# homeboard10.net
KiCad netlist of a schematic drawn in EAGLE
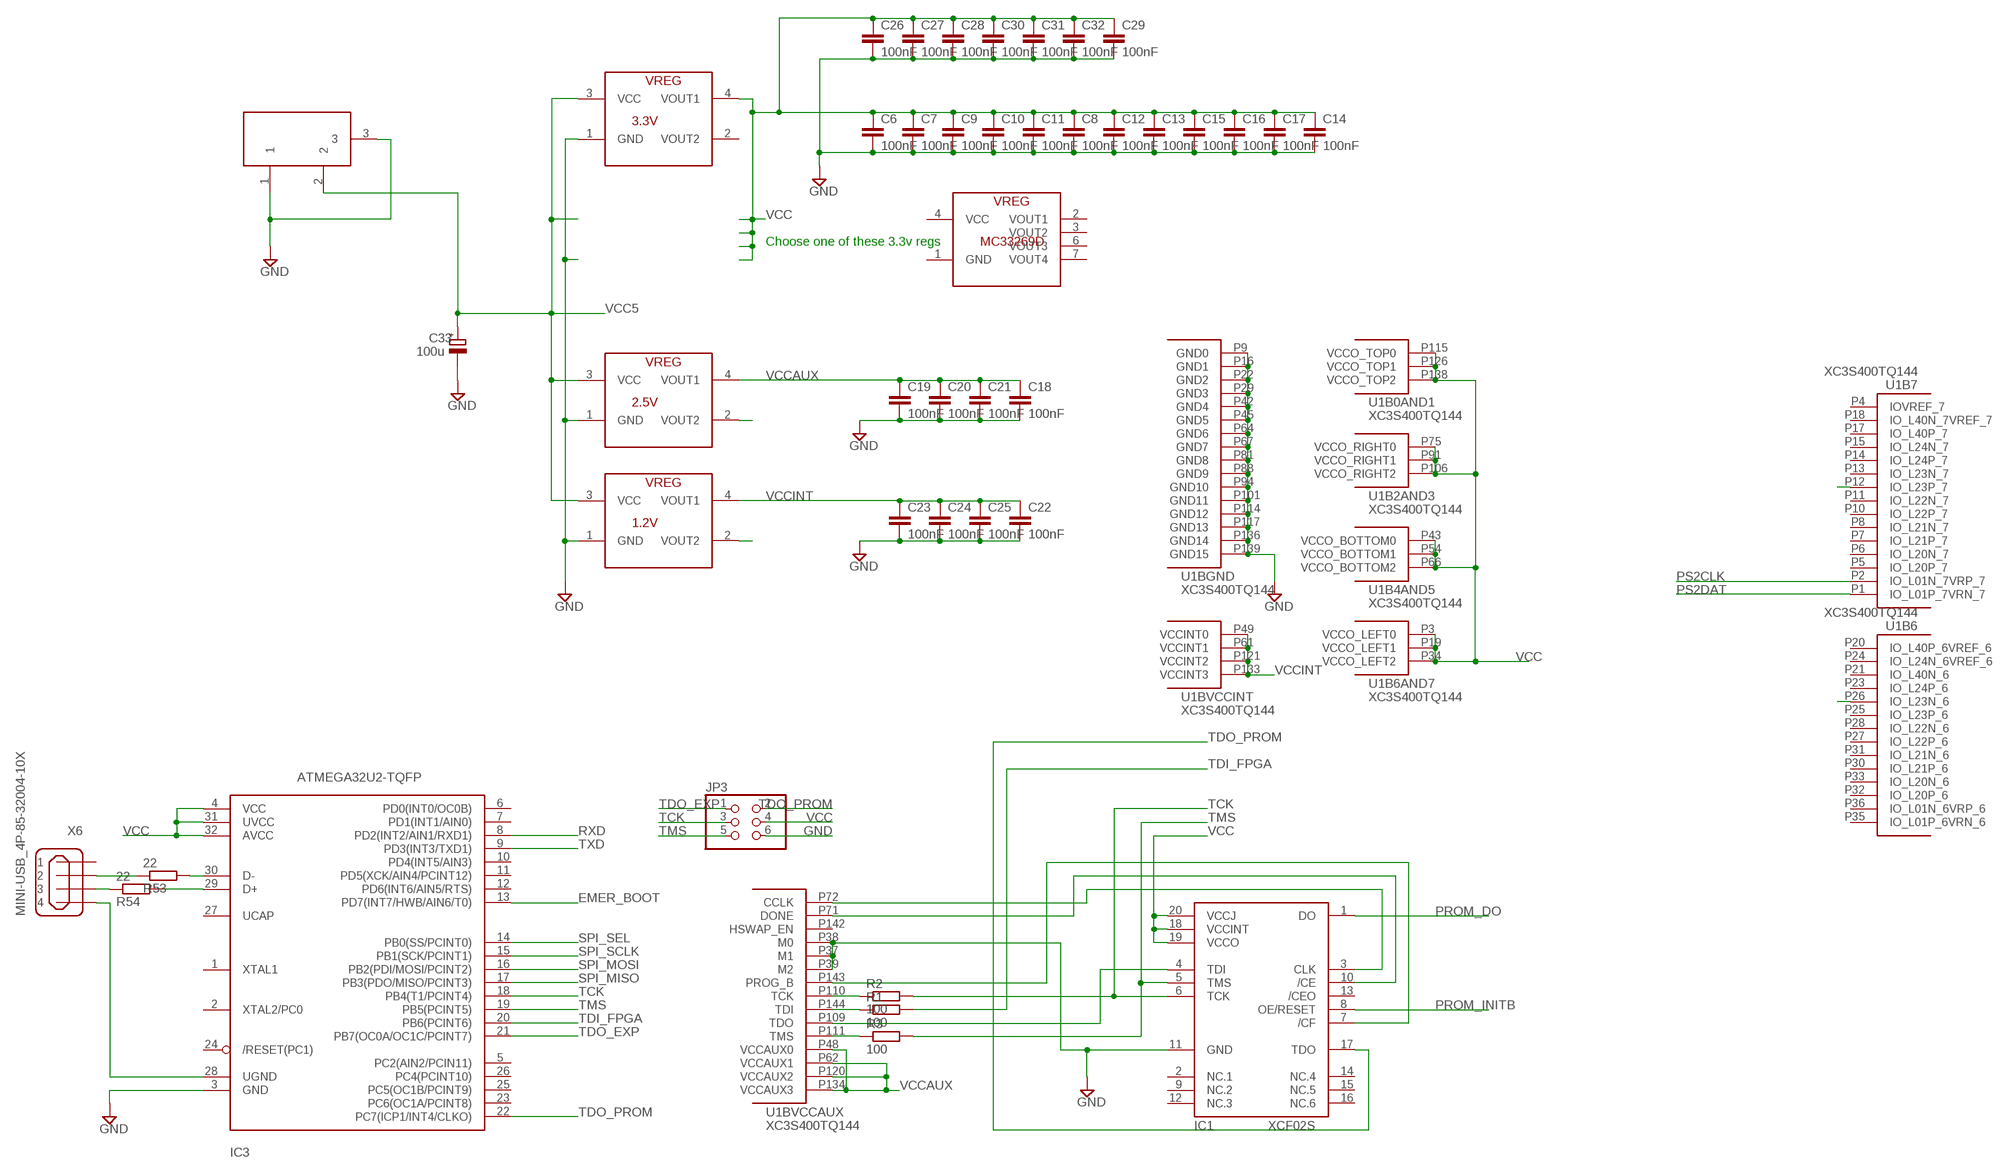
[diagram p0: schematic, sheet 1, part 1 of 3]
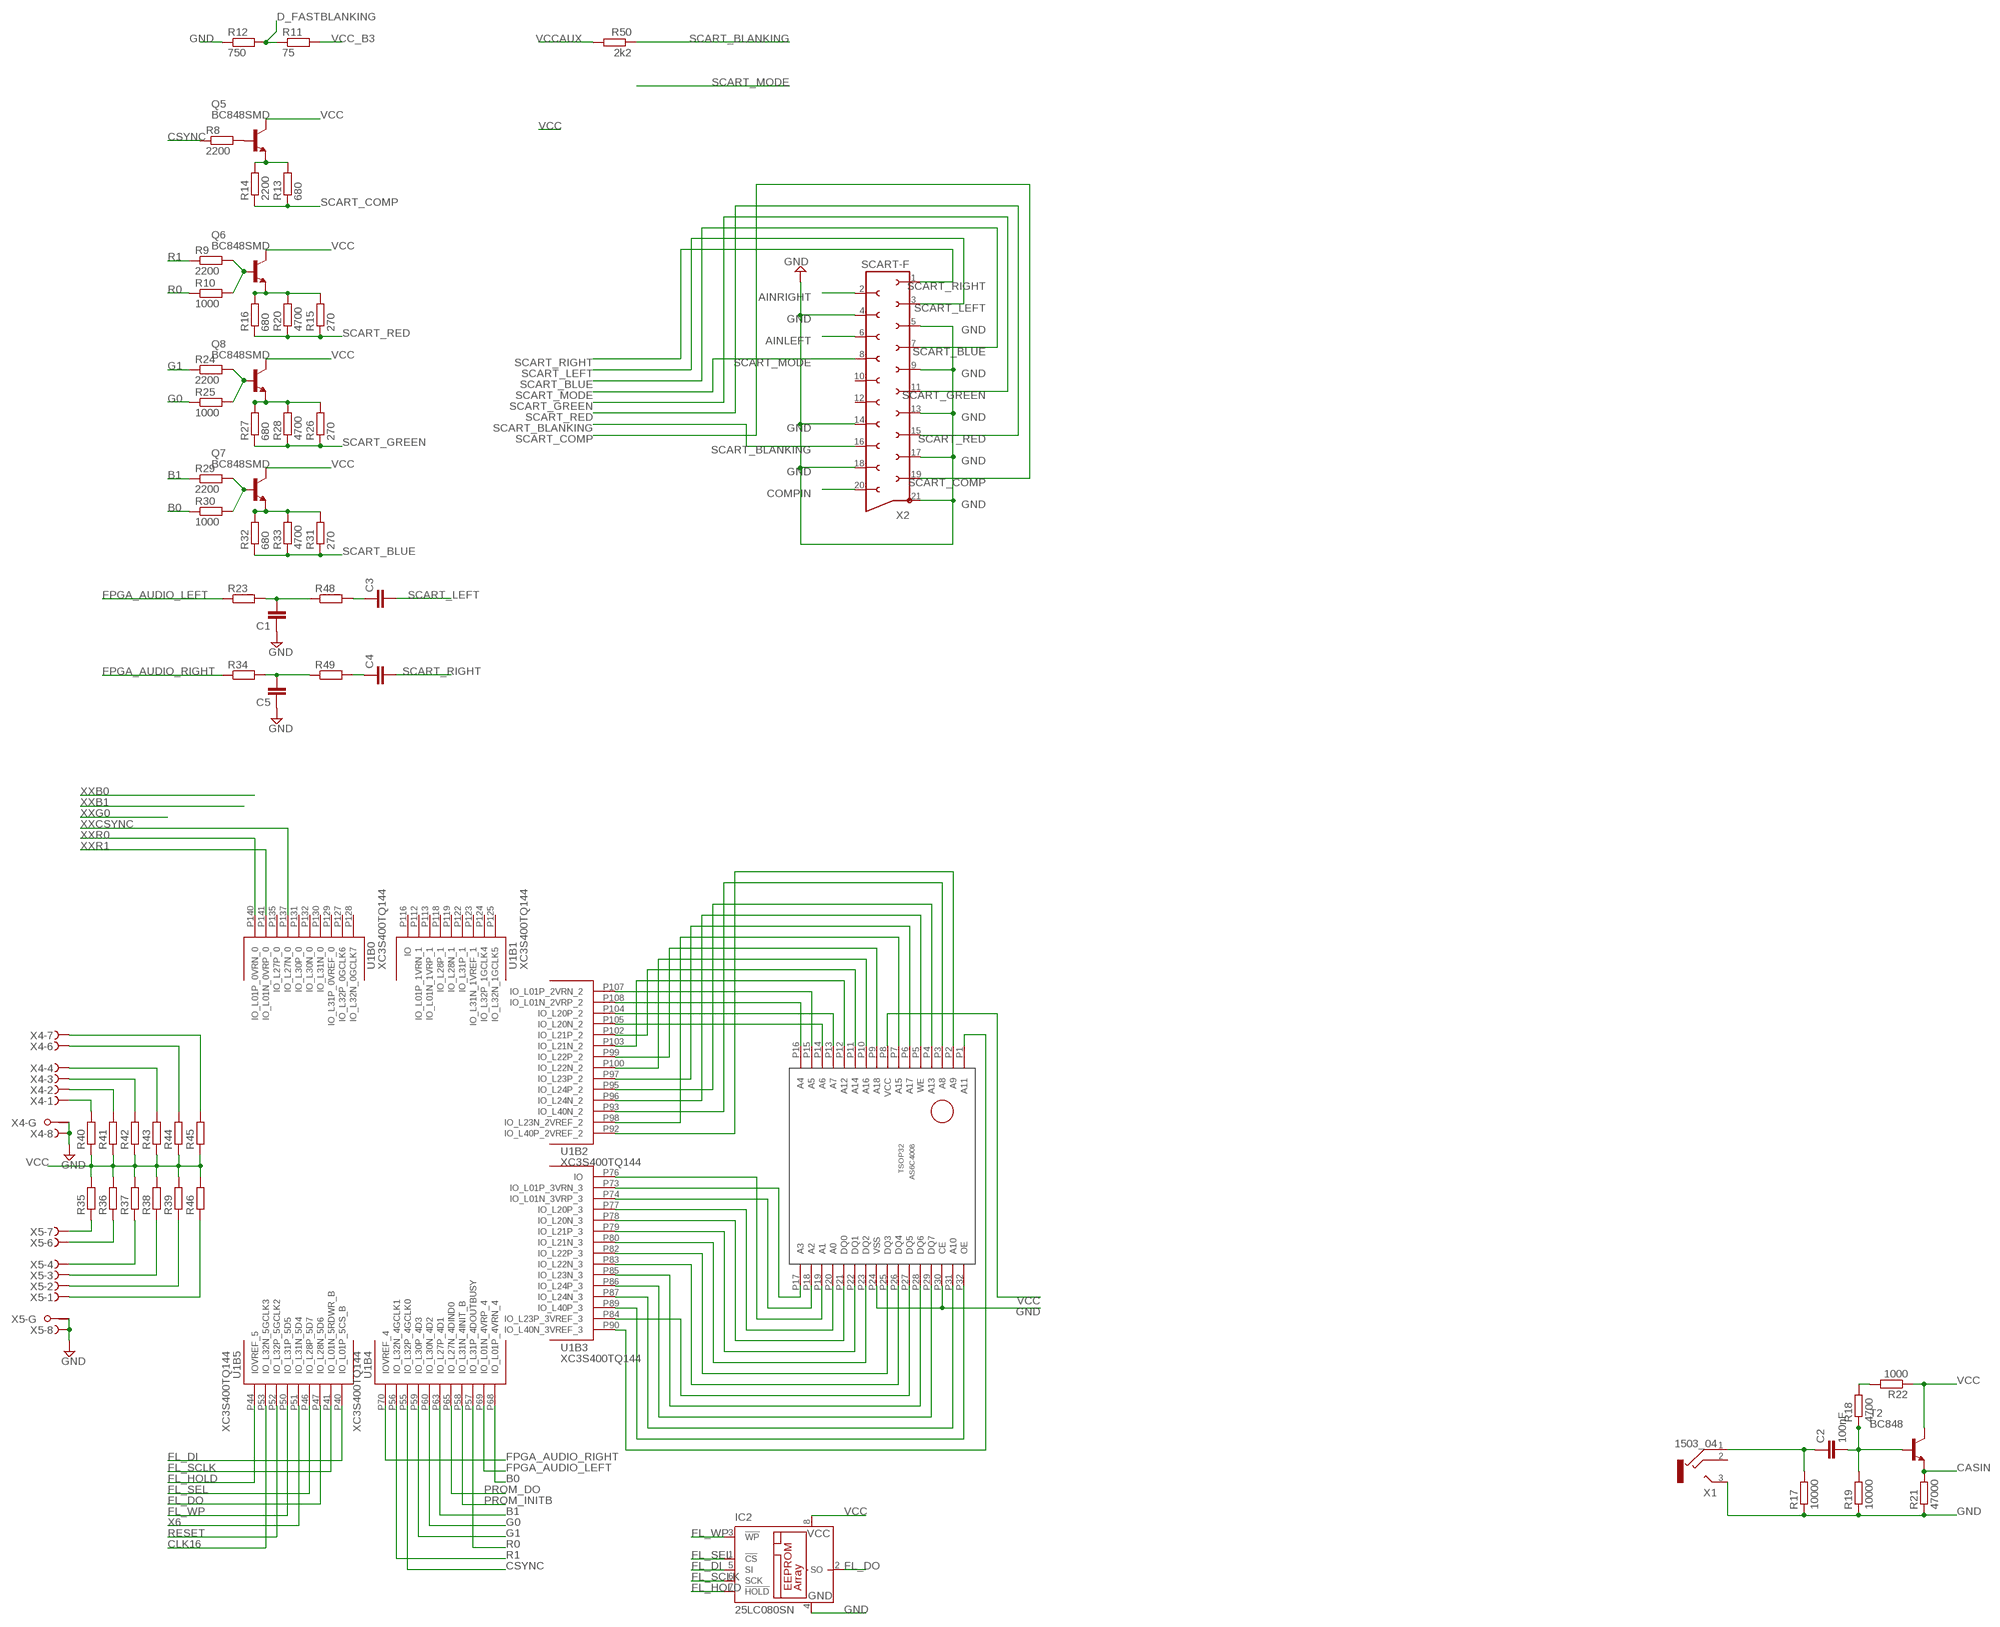
[diagram p1: schematic, sheet 1, part 2 of 3]
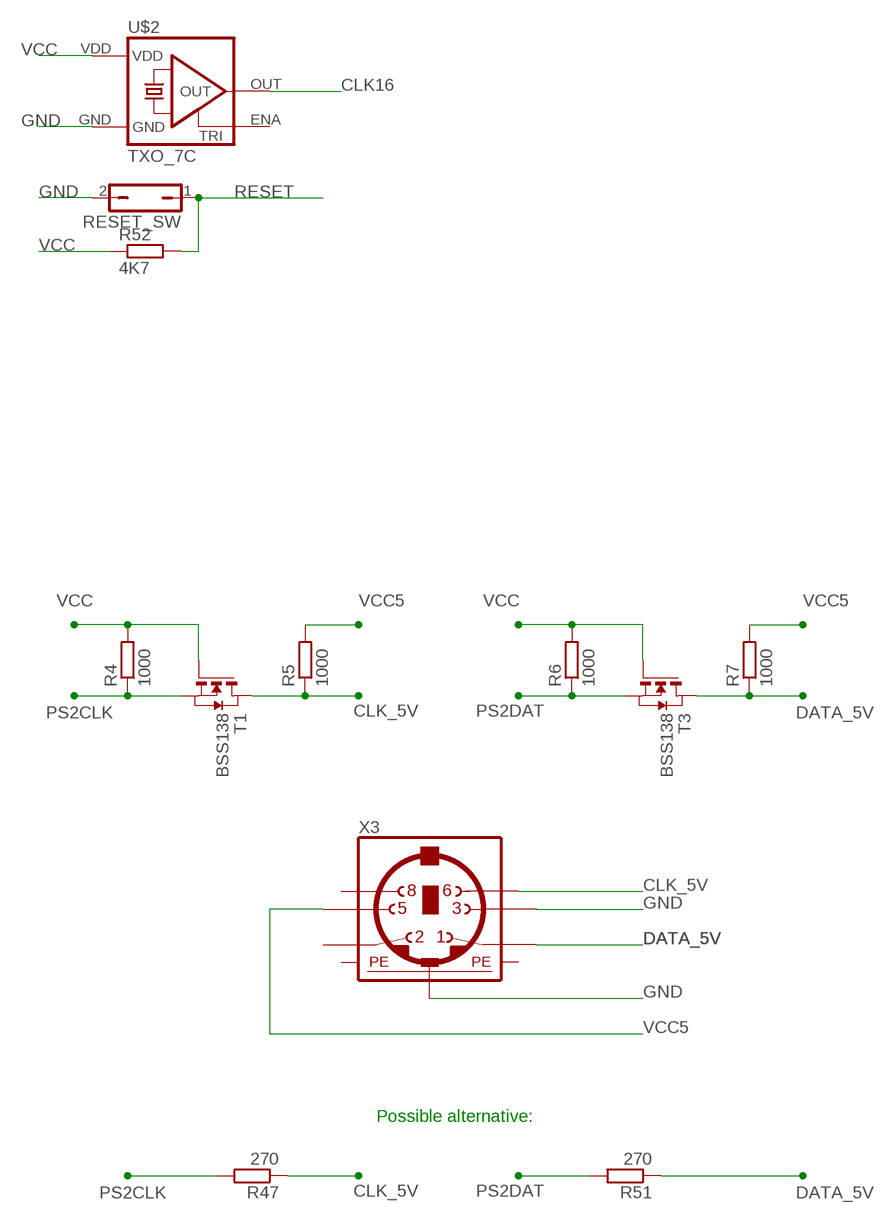
[diagram p2: schematic, sheet 1, part 3 of 3]

(export (version "E")
  (design (tool "Eeschema 10.0.6"))
  (components
    (comp (ref "C1")
      (value "C-EUC0603")
      (footprint "eagle-import:C0603")
      (libsource (lib "eagle-import") (part "resistor_C-EUC0603"))
    )
    (comp (ref "C2")
      (value "100nF")
      (footprint "eagle-import:C0603")
      (libsource (lib "eagle-import") (part "resistor_C-EUC0603"))
    )
    (comp (ref "C3")
      (value "C-EUC0603")
      (footprint "eagle-import:C0603")
      (libsource (lib "eagle-import") (part "resistor_C-EUC0603"))
    )
    (comp (ref "C4")
      (value "C-EUC0603")
      (footprint "eagle-import:C0603")
      (libsource (lib "eagle-import") (part "resistor_C-EUC0603"))
    )
    (comp (ref "C5")
      (value "C-EUC0603")
      (footprint "eagle-import:C0603")
      (libsource (lib "eagle-import") (part "resistor_C-EUC0603"))
    )
    (comp (ref "C6")
      (value "100nF")
      (footprint "eagle-import:C0603")
      (libsource (lib "eagle-import") (part "C-EUC0603"))
    )
    (comp (ref "C7")
      (value "100nF")
      (footprint "eagle-import:C0603")
      (libsource (lib "eagle-import") (part "C-EUC0603"))
    )
    (comp (ref "C8")
      (value "100nF")
      (footprint "eagle-import:C0603")
      (libsource (lib "eagle-import") (part "C-EUC0603"))
    )
    (comp (ref "C9")
      (value "100nF")
      (footprint "eagle-import:C0603")
      (libsource (lib "eagle-import") (part "C-EUC0603"))
    )
    (comp (ref "C10")
      (value "100nF")
      (footprint "eagle-import:C0603")
      (libsource (lib "eagle-import") (part "C-EUC0603"))
    )
    (comp (ref "C11")
      (value "100nF")
      (footprint "eagle-import:C0603")
      (libsource (lib "eagle-import") (part "C-EUC0603"))
    )
    (comp (ref "C12")
      (value "100nF")
      (footprint "eagle-import:C0603")
      (libsource (lib "eagle-import") (part "C-EUC0603"))
    )
    (comp (ref "C13")
      (value "100nF")
      (footprint "eagle-import:C0603")
      (libsource (lib "eagle-import") (part "C-EUC0603"))
    )
    (comp (ref "C14")
      (value "100nF")
      (footprint "eagle-import:C0603")
      (libsource (lib "eagle-import") (part "C-EUC0603"))
    )
    (comp (ref "C15")
      (value "100nF")
      (footprint "eagle-import:C0603")
      (libsource (lib "eagle-import") (part "C-EUC0603"))
    )
    (comp (ref "C16")
      (value "100nF")
      (footprint "eagle-import:C0603")
      (libsource (lib "eagle-import") (part "C-EUC0603"))
    )
    (comp (ref "C17")
      (value "100nF")
      (footprint "eagle-import:C0603")
      (libsource (lib "eagle-import") (part "C-EUC0603"))
    )
    (comp (ref "C18")
      (value "100nF")
      (footprint "eagle-import:C0603")
      (libsource (lib "eagle-import") (part "C-EUC0603"))
    )
    (comp (ref "C19")
      (value "100nF")
      (footprint "eagle-import:C0603")
      (libsource (lib "eagle-import") (part "C-EUC0603"))
    )
    (comp (ref "C20")
      (value "100nF")
      (footprint "eagle-import:C0603")
      (libsource (lib "eagle-import") (part "C-EUC0603"))
    )
    (comp (ref "C21")
      (value "100nF")
      (footprint "eagle-import:C0603")
      (libsource (lib "eagle-import") (part "C-EUC0603"))
    )
    (comp (ref "C22")
      (value "100nF")
      (footprint "eagle-import:C0603")
      (libsource (lib "eagle-import") (part "C-EUC0603"))
    )
    (comp (ref "C23")
      (value "100nF")
      (footprint "eagle-import:C0603")
      (libsource (lib "eagle-import") (part "C-EUC0603"))
    )
    (comp (ref "C24")
      (value "100nF")
      (footprint "eagle-import:C0603")
      (libsource (lib "eagle-import") (part "C-EUC0603"))
    )
    (comp (ref "C25")
      (value "100nF")
      (footprint "eagle-import:C0603")
      (libsource (lib "eagle-import") (part "C-EUC0603"))
    )
    (comp (ref "C26")
      (value "100nF")
      (footprint "eagle-import:C0603")
      (libsource (lib "eagle-import") (part "C-EUC0603"))
    )
    (comp (ref "C27")
      (value "100nF")
      (footprint "eagle-import:C0603")
      (libsource (lib "eagle-import") (part "C-EUC0603"))
    )
    (comp (ref "C28")
      (value "100nF")
      (footprint "eagle-import:C0603")
      (libsource (lib "eagle-import") (part "C-EUC0603"))
    )
    (comp (ref "C29")
      (value "100nF")
      (footprint "eagle-import:C0603")
      (libsource (lib "eagle-import") (part "C-EUC0603"))
    )
    (comp (ref "C30")
      (value "100nF")
      (footprint "eagle-import:C0603")
      (libsource (lib "eagle-import") (part "C-EUC0603"))
    )
    (comp (ref "C31")
      (value "100nF")
      (footprint "eagle-import:C0603")
      (libsource (lib "eagle-import") (part "C-EUC0603"))
    )
    (comp (ref "C32")
      (value "100nF")
      (footprint "eagle-import:C0603")
      (libsource (lib "eagle-import") (part "C-EUC0603"))
    )
    (comp (ref "C33")
      (value "100u")
      (footprint "eagle-import:PANASONIC_D")
      (libsource (lib "eagle-import") (part "CPOL-EUD"))
    )
    (comp (ref "IC1")
      (value "XCF02S")
      (footprint "eagle-import:VO20")
      (libsource (lib "eagle-import") (part "XCF02S"))
    )
    (comp (ref "IC2")
      (value "25LC080SN")
      (footprint "eagle-import:SO-08")
      (fields (field (name "MF") "MICROCHIP") (field (name "MPN") "25LC080/SN"))
      (libsource (lib "eagle-import") (part "25SNLC080"))
    )
    (comp (ref "IC3")
      (value "ATMEGA32U2-TQFP")
      (footprint "eagle-import:TQFP32-08")
      (libsource (lib "eagle-import") (part "ATMEGA32U2-TQFP"))
    )
    (comp (ref "JP3")
      (value "PINHD-2X3")
      (footprint "eagle-import:2X03")
      (libsource (lib "eagle-import") (part "PINHD-2X3"))
    )
    (comp (ref "Q5")
      (value "BC848SMD")
      (footprint "eagle-import:SOT23")
      (libsource (lib "eagle-import") (part "BC848SMD"))
    )
    (comp (ref "Q6")
      (value "BC848SMD")
      (footprint "eagle-import:SOT23")
      (libsource (lib "eagle-import") (part "BC848SMD"))
    )
    (comp (ref "Q7")
      (value "BC848SMD")
      (footprint "eagle-import:SOT23")
      (libsource (lib "eagle-import") (part "BC848SMD"))
    )
    (comp (ref "Q8")
      (value "BC848SMD")
      (footprint "eagle-import:SOT23")
      (libsource (lib "eagle-import") (part "BC848SMD"))
    )
    (comp (ref "R1")
      (value "100")
      (footprint "eagle-import:R0805")
      (libsource (lib "eagle-import") (part "R-EU_R0805"))
    )
    (comp (ref "R2")
      (value "100")
      (footprint "eagle-import:R0805")
      (libsource (lib "eagle-import") (part "R-EU_R0805"))
    )
    (comp (ref "R3")
      (value "100")
      (footprint "eagle-import:R0805")
      (libsource (lib "eagle-import") (part "R-EU_R0805"))
    )
    (comp (ref "R4")
      (value "1000")
      (footprint "eagle-import:R0805")
      (libsource (lib "eagle-import") (part "R-EU_R0805"))
    )
    (comp (ref "R5")
      (value "1000")
      (footprint "eagle-import:R0805")
      (libsource (lib "eagle-import") (part "R-EU_R0805"))
    )
    (comp (ref "R6")
      (value "1000")
      (footprint "eagle-import:R0805")
      (libsource (lib "eagle-import") (part "R-EU_R0805"))
    )
    (comp (ref "R7")
      (value "1000")
      (footprint "eagle-import:R0805")
      (libsource (lib "eagle-import") (part "R-EU_R0805"))
    )
    (comp (ref "R8")
      (value "2200")
      (footprint "eagle-import:R0805")
      (libsource (lib "eagle-import") (part "R-EU_R0805"))
    )
    (comp (ref "R9")
      (value "2200")
      (footprint "eagle-import:R0805")
      (libsource (lib "eagle-import") (part "R-EU_R0805"))
    )
    (comp (ref "R10")
      (value "1000")
      (footprint "eagle-import:R0805")
      (libsource (lib "eagle-import") (part "R-EU_R0805"))
    )
    (comp (ref "R11")
      (value "75")
      (footprint "eagle-import:R0805")
      (libsource (lib "eagle-import") (part "R-EU_R0805"))
    )
    (comp (ref "R12")
      (value "750")
      (footprint "eagle-import:R0805")
      (libsource (lib "eagle-import") (part "R-EU_R0805"))
    )
    (comp (ref "R13")
      (value "680")
      (footprint "eagle-import:R0805")
      (libsource (lib "eagle-import") (part "R-EU_R0805"))
    )
    (comp (ref "R14")
      (value "2200")
      (footprint "eagle-import:R0805")
      (libsource (lib "eagle-import") (part "R-EU_R0805"))
    )
    (comp (ref "R15")
      (value "270")
      (footprint "eagle-import:R0805")
      (libsource (lib "eagle-import") (part "R-EU_R0805"))
    )
    (comp (ref "R16")
      (value "680")
      (footprint "eagle-import:R0805")
      (libsource (lib "eagle-import") (part "R-EU_R0805"))
    )
    (comp (ref "R17")
      (value "10000")
      (footprint "eagle-import:R0805")
      (libsource (lib "eagle-import") (part "R-EU_R0805"))
    )
    (comp (ref "R18")
      (value "4700")
      (footprint "eagle-import:R0805")
      (libsource (lib "eagle-import") (part "R-EU_R0805"))
    )
    (comp (ref "R19")
      (value "10000")
      (footprint "eagle-import:R0805")
      (libsource (lib "eagle-import") (part "R-EU_R0805"))
    )
    (comp (ref "R20")
      (value "4700")
      (footprint "eagle-import:R0805")
      (libsource (lib "eagle-import") (part "R-EU_R0805"))
    )
    (comp (ref "R21")
      (value "47000")
      (footprint "eagle-import:R0805")
      (libsource (lib "eagle-import") (part "R-EU_R0805"))
    )
    (comp (ref "R22")
      (value "1000")
      (footprint "eagle-import:R0805")
      (libsource (lib "eagle-import") (part "R-EU_R0805"))
    )
    (comp (ref "R23")
      (value "R-EU_M0805")
      (footprint "eagle-import:M0805")
      (libsource (lib "eagle-import") (part "resistor_R-EU_M0805"))
    )
    (comp (ref "R24")
      (value "2200")
      (footprint "eagle-import:R0805")
      (libsource (lib "eagle-import") (part "R-EU_R0805"))
    )
    (comp (ref "R25")
      (value "1000")
      (footprint "eagle-import:R0805")
      (libsource (lib "eagle-import") (part "R-EU_R0805"))
    )
    (comp (ref "R26")
      (value "270")
      (footprint "eagle-import:R0805")
      (libsource (lib "eagle-import") (part "R-EU_R0805"))
    )
    (comp (ref "R27")
      (value "680")
      (footprint "eagle-import:R0805")
      (libsource (lib "eagle-import") (part "R-EU_R0805"))
    )
    (comp (ref "R28")
      (value "4700")
      (footprint "eagle-import:R0805")
      (libsource (lib "eagle-import") (part "R-EU_R0805"))
    )
    (comp (ref "R29")
      (value "2200")
      (footprint "eagle-import:R0805")
      (libsource (lib "eagle-import") (part "R-EU_R0805"))
    )
    (comp (ref "R30")
      (value "1000")
      (footprint "eagle-import:R0805")
      (libsource (lib "eagle-import") (part "R-EU_R0805"))
    )
    (comp (ref "R31")
      (value "270")
      (footprint "eagle-import:R0805")
      (libsource (lib "eagle-import") (part "R-EU_R0805"))
    )
    (comp (ref "R32")
      (value "680")
      (footprint "eagle-import:R0805")
      (libsource (lib "eagle-import") (part "R-EU_R0805"))
    )
    (comp (ref "R33")
      (value "4700")
      (footprint "eagle-import:R0805")
      (libsource (lib "eagle-import") (part "R-EU_R0805"))
    )
    (comp (ref "R34")
      (value "R-EU_M0805")
      (footprint "eagle-import:M0805")
      (libsource (lib "eagle-import") (part "resistor_R-EU_M0805"))
    )
    (comp (ref "R35")
      (value "R-EU_M0805")
      (footprint "eagle-import:M0805")
      (libsource (lib "eagle-import") (part "resistor_R-EU_M0805"))
    )
    (comp (ref "R36")
      (value "R-EU_M0805")
      (footprint "eagle-import:M0805")
      (libsource (lib "eagle-import") (part "resistor_R-EU_M0805"))
    )
    (comp (ref "R37")
      (value "R-EU_M0805")
      (footprint "eagle-import:M0805")
      (libsource (lib "eagle-import") (part "resistor_R-EU_M0805"))
    )
    (comp (ref "R38")
      (value "R-EU_M0805")
      (footprint "eagle-import:M0805")
      (libsource (lib "eagle-import") (part "resistor_R-EU_M0805"))
    )
    (comp (ref "R39")
      (value "R-EU_M0805")
      (footprint "eagle-import:M0805")
      (libsource (lib "eagle-import") (part "resistor_R-EU_M0805"))
    )
    (comp (ref "R40")
      (value "R-EU_M0805")
      (footprint "eagle-import:M0805")
      (libsource (lib "eagle-import") (part "resistor_R-EU_M0805"))
    )
    (comp (ref "R41")
      (value "R-EU_M0805")
      (footprint "eagle-import:M0805")
      (libsource (lib "eagle-import") (part "resistor_R-EU_M0805"))
    )
    (comp (ref "R42")
      (value "R-EU_M0805")
      (footprint "eagle-import:M0805")
      (libsource (lib "eagle-import") (part "resistor_R-EU_M0805"))
    )
    (comp (ref "R43")
      (value "R-EU_M0805")
      (footprint "eagle-import:M0805")
      (libsource (lib "eagle-import") (part "resistor_R-EU_M0805"))
    )
    (comp (ref "R44")
      (value "R-EU_M0805")
      (footprint "eagle-import:M0805")
      (libsource (lib "eagle-import") (part "resistor_R-EU_M0805"))
    )
    (comp (ref "R45")
      (value "R-EU_M0805")
      (footprint "eagle-import:M0805")
      (libsource (lib "eagle-import") (part "resistor_R-EU_M0805"))
    )
    (comp (ref "R46")
      (value "R-EU_M0805")
      (footprint "eagle-import:M0805")
      (libsource (lib "eagle-import") (part "resistor_R-EU_M0805"))
    )
    (comp (ref "R47")
      (value "270")
      (footprint "eagle-import:R0805")
      (libsource (lib "eagle-import") (part "R-EU_R0805"))
    )
    (comp (ref "R48")
      (value "R-EU_M0805")
      (footprint "eagle-import:M0805")
      (libsource (lib "eagle-import") (part "resistor_R-EU_M0805"))
    )
    (comp (ref "R49")
      (value "R-EU_M0805")
      (footprint "eagle-import:M0805")
      (libsource (lib "eagle-import") (part "resistor_R-EU_M0805"))
    )
    (comp (ref "R50")
      (value "2k2")
      (footprint "eagle-import:M0805")
      (libsource (lib "eagle-import") (part "resistor_R-EU_M0805"))
    )
    (comp (ref "R51")
      (value "270")
      (footprint "eagle-import:R0805")
      (libsource (lib "eagle-import") (part "R-EU_R0805"))
    )
    (comp (ref "R52")
      (value "4K7")
      (footprint "eagle-import:M0805")
      (libsource (lib "eagle-import") (part "resistor_R-EU_M0805"))
    )
    (comp (ref "R53")
      (value "22")
      (footprint "eagle-import:R0805")
      (libsource (lib "eagle-import") (part "R-EU_R0805"))
    )
    (comp (ref "R54")
      (value "22")
      (footprint "eagle-import:R0805")
      (libsource (lib "eagle-import") (part "R-EU_R0805"))
    )
    (comp (ref "REG1.2")
      (value "1.2V")
      (footprint "eagle-import:SOT223")
      (libsource (lib "eagle-import") (part "NX1117"))
    )
    (comp (ref "REG2.5")
      (value "2.5V")
      (footprint "eagle-import:SOT223")
      (libsource (lib "eagle-import") (part "NX1117"))
    )
    (comp (ref "RESET_SW")
      (value "JP1Q")
      (footprint "eagle-import:JP1")
      (libsource (lib "eagle-import") (part "JP1Q"))
    )
    (comp (ref "T1")
      (value "BSS138")
      (footprint "eagle-import:SOT-23")
      (libsource (lib "eagle-import") (part "NMOSSOT23"))
    )
    (comp (ref "T2")
      (value "BC848")
      (footprint "eagle-import:SOT23")
      (libsource (lib "eagle-import") (part "BC848"))
    )
    (comp (ref "T3")
      (value "BSS138")
      (footprint "eagle-import:SOT-23")
      (libsource (lib "eagle-import") (part "NMOSSOT23"))
    )
    (comp (ref "U$1")
      (value "AS6C4008")
      (footprint "eagle-import:TSOP32")
      (libsource (lib "eagle-import") (part "AS6C4008"))
    )
    (comp (ref "U$2")
      (value "TXO_7C")
      (footprint "eagle-import:OSC_7C")
      (libsource (lib "eagle-import") (part "TXO_7C"))
    )
    (comp (ref "U$4")
      (value "3.3V")
      (footprint "eagle-import:SOT223")
      (libsource (lib "eagle-import") (part "NX1117"))
    )
    (comp (ref "U$5")
      (value "MC33269D")
      (footprint "eagle-import:SO8")
      (libsource (lib "eagle-import") (part "MC33269D"))
    )
    (comp (ref "U1")
      (value "XC3S400TQ144")
      (footprint "eagle-import:TQ144")
      (libsource (lib "eagle-import") (part "XC3S400TQ144"))
    )
    (comp (ref "X1")
      (value "1503_04")
      (footprint "eagle-import:1503_04")
      (libsource (lib "eagle-import") (part "1503_04"))
    )
    (comp (ref "X2")
      (value "SCART-F")
      (footprint "eagle-import:SCART-F")
      (libsource (lib "eagle-import") (part "SCART-F"))
    )
    (comp (ref "X3")
      (value "MINI_DIN_6")
      (footprint "eagle-import:M_DIN6")
      (libsource (lib "eagle-import") (part "MINI_DIN_6"))
    )
    (comp (ref "X4")
      (value "F09HPS")
      (footprint "eagle-import:F09HP")
      (libsource (lib "eagle-import") (part "F09HPS"))
    )
    (comp (ref "X5")
      (value "F09HPS")
      (footprint "eagle-import:F09HP")
      (libsource (lib "eagle-import") (part "F09HPS"))
    )
    (comp (ref "X6")
      (value "MINI-USB_4P-85-32004-10X")
      (footprint "eagle-import:85-32004-10X")
      (libsource (lib "eagle-import") (part "MINI-USB_4P-85-32004-10X"))
    )
    (comp (ref "X8")
      (value "DC21MMX")
      (footprint "eagle-import:DC-21MM")
      (libsource (lib "eagle-import") (part "DC21MMX"))
    )
  )
  (nets
    (net (code "1") (name "/AINLEFT") (class "Default")
      (node (ref "X2") (pin "6") (pinfunction "6_6") (pintype "passive"))
    )
    (net (code "2") (name "/AINRIGHT") (class "Default")
      (node (ref "X2") (pin "2") (pinfunction "2_2") (pintype "passive"))
    )
    (net (code "3") (name "/B0") (class "Default")
      (node (ref "R30") (pin "1") (pinfunction "1_1") (pintype "passive"))
      (node (ref "U1") (pin "P68") (pinfunction "IO_L01P_4VRN_4_P68") (pintype "bidirectional"))
    )
    (net (code "4") (name "/B1") (class "Default")
      (node (ref "R29") (pin "1") (pinfunction "1_1") (pintype "passive"))
      (node (ref "U1") (pin "P63") (pinfunction "IO_L27P_4D1_P63") (pintype "bidirectional"))
    )
    (net (code "5") (name "/CASIN") (class "Default")
      (node (ref "R21") (pin "2") (pinfunction "2_2") (pintype "passive"))
      (node (ref "T2") (pin "2") (pinfunction "E_2") (pintype "passive"))
    )
    (net (code "6") (name "/CLK16") (class "Default")
      (node (ref "U$2") (pin "OUT") (pinfunction "OUT_OUT") (pintype "output"))
      (node (ref "U1") (pin "P53") (pinfunction "IO_L32N_5GCLK3_P53") (pintype "bidirectional"))
    )
    (net (code "7") (name "/CLK_5V") (class "Default")
      (node (ref "R47") (pin "1") (pinfunction "1_1") (pintype "passive"))
      (node (ref "R5") (pin "1") (pinfunction "1_1") (pintype "passive"))
      (node (ref "T1") (pin "1") (pinfunction "D_1") (pintype "passive"))
      (node (ref "X3") (pin "6") (pinfunction "6_6") (pintype "passive"))
    )
    (net (code "8") (name "/COMPIN") (class "Default")
      (node (ref "X2") (pin "20") (pinfunction "20_20") (pintype "passive"))
    )
    (net (code "9") (name "/CSYNC") (class "Default")
      (node (ref "R8") (pin "1") (pinfunction "1_1") (pintype "passive"))
      (node (ref "U1") (pin "P55") (pinfunction "IO_L32P_4GCLK0_P55") (pintype "bidirectional"))
    )
    (net (code "10") (name "/DATA_5V") (class "Default")
      (node (ref "R51") (pin "1") (pinfunction "1_1") (pintype "passive"))
      (node (ref "R7") (pin "1") (pinfunction "1_1") (pintype "passive"))
      (node (ref "T3") (pin "1") (pinfunction "D_1") (pintype "passive"))
      (node (ref "X3") (pin "1") (pinfunction "1_1") (pintype "passive"))
    )
    (net (code "11") (name "/D_FASTBLANKING") (class "Default")
      (node (ref "R11") (pin "1") (pinfunction "1_1") (pintype "passive"))
      (node (ref "R12") (pin "2") (pinfunction "2_2") (pintype "passive"))
    )
    (net (code "12") (name "/EMER_BOOT") (class "Default")
      (node (ref "IC3") (pin "13") (pinfunction "PD7(INT7/HWB/AIN6/T0)_13") (pintype "bidirectional"))
    )
    (net (code "13") (name "/FL_DI") (class "Default")
      (node (ref "IC2") (pin "5") (pinfunction "SI_5") (pintype "input"))
      (node (ref "U1") (pin "P40") (pinfunction "IO_L01P_5CS_B_P40") (pintype "bidirectional"))
    )
    (net (code "14") (name "/FL_DO") (class "Default")
      (node (ref "IC2") (pin "2") (pinfunction "SO_2") (pintype "bidirectional"))
      (node (ref "U1") (pin "P47") (pinfunction "IO_L28N_5D6_P47") (pintype "bidirectional"))
    )
    (net (code "15") (name "/FL_HOLD") (class "Default")
      (node (ref "IC2") (pin "7") (pinfunction "~{HOLD}_7") (pintype "input"))
      (node (ref "U1") (pin "P44") (pinfunction "IOVREF_5_P44") (pintype "bidirectional"))
    )
    (net (code "16") (name "/FL_SCLK") (class "Default")
      (node (ref "IC2") (pin "6") (pinfunction "SCK_6") (pintype "input"))
      (node (ref "U1") (pin "P41") (pinfunction "IO_L01N_5RDWR_B_P41") (pintype "bidirectional"))
    )
    (net (code "17") (name "/FL_SEL") (class "Default")
      (node (ref "IC2") (pin "1") (pinfunction "~{CS}_1") (pintype "input"))
      (node (ref "U1") (pin "P46") (pinfunction "IO_L28P_5D7_P46") (pintype "bidirectional"))
    )
    (net (code "18") (name "/FL_WP") (class "Default")
      (node (ref "IC2") (pin "3") (pinfunction "~{WP}_3") (pintype "input"))
      (node (ref "U1") (pin "P50") (pinfunction "IO_L31P_5D5_P50") (pintype "bidirectional"))
    )
    (net (code "19") (name "/FPGA_AUDIO_LEFT") (class "Default")
      (node (ref "R23") (pin "1") (pinfunction "1_1") (pintype "passive"))
      (node (ref "U1") (pin "P69") (pinfunction "IO_L01N_4VRP_4_P69") (pintype "bidirectional"))
    )
    (net (code "20") (name "/FPGA_AUDIO_RIGHT") (class "Default")
      (node (ref "R34") (pin "1") (pinfunction "1_1") (pintype "passive"))
      (node (ref "U1") (pin "P70") (pinfunction "IOVREF_4_P70") (pintype "bidirectional"))
    )
    (net (code "21") (name "/G0") (class "Default")
      (node (ref "R25") (pin "1") (pinfunction "1_1") (pintype "passive"))
      (node (ref "U1") (pin "P60") (pinfunction "IO_L30N_4D2_P60") (pintype "bidirectional"))
    )
    (net (code "22") (name "/G1") (class "Default")
      (node (ref "R24") (pin "1") (pinfunction "1_1") (pintype "passive"))
      (node (ref "U1") (pin "P59") (pinfunction "IO_L30P_4D3_P59") (pintype "bidirectional"))
    )
    (net (code "23") (name "/PE1") (class "Default")
      (node (ref "X3") (pin "SH1") (pinfunction "PE1_SH1") (pintype "power_in"))
    )
    (net (code "24") (name "/PE3") (class "Default")
      (node (ref "X3") (pin "SH3") (pinfunction "PE3_SH3") (pintype "power_in"))
    )
    (net (code "25") (name "/PROM_DO") (class "Default")
      (node (ref "IC1") (pin "1") (pinfunction "DO_1") (pintype "bidirectional"))
      (node (ref "U1") (pin "P65") (pinfunction "IO_L27N_4DIND0_P65") (pintype "bidirectional"))
    )
    (net (code "26") (name "/PROM_INITB") (class "Default")
      (node (ref "IC1") (pin "8") (pinfunction "OE/RESET_8") (pintype "bidirectional"))
      (node (ref "U1") (pin "P58") (pinfunction "IO_L31N_4INIT_B_P58") (pintype "bidirectional"))
    )
    (net (code "27") (name "/PS2CLK") (class "Default")
      (node (ref "R4") (pin "1") (pinfunction "1_1") (pintype "passive"))
      (node (ref "R47") (pin "2") (pinfunction "2_2") (pintype "passive"))
      (node (ref "T1") (pin "2") (pinfunction "S_2") (pintype "passive"))
      (node (ref "U1") (pin "P2") (pinfunction "IO_L01N_7VRP_7_P2") (pintype "bidirectional"))
    )
    (net (code "28") (name "/PS2DAT") (class "Default")
      (node (ref "R51") (pin "2") (pinfunction "2_2") (pintype "passive"))
      (node (ref "R6") (pin "1") (pinfunction "1_1") (pintype "passive"))
      (node (ref "T3") (pin "2") (pinfunction "S_2") (pintype "passive"))
      (node (ref "U1") (pin "P1") (pinfunction "IO_L01P_7VRN_7_P1") (pintype "bidirectional"))
    )
    (net (code "29") (name "/R0") (class "Default")
      (node (ref "R10") (pin "1") (pinfunction "1_1") (pintype "passive"))
      (node (ref "U1") (pin "P57") (pinfunction "IO_L31P_4DOUTBUSY_P57") (pintype "bidirectional"))
    )
    (net (code "30") (name "/R1") (class "Default")
      (node (ref "R9") (pin "1") (pinfunction "1_1") (pintype "passive"))
      (node (ref "U1") (pin "P56") (pinfunction "IO_L32N_4GCLK1_P56") (pintype "bidirectional"))
    )
    (net (code "31") (name "/RESET") (class "Default")
      (node (ref "R52") (pin "2") (pinfunction "2_2") (pintype "passive"))
      (node (ref "RESET_SW") (pin "1") (pinfunction "1_1") (pintype "passive"))
      (node (ref "U1") (pin "P52") (pinfunction "IO_L32P_5GCLK2_P52") (pintype "bidirectional"))
    )
    (net (code "32") (name "/RXD") (class "Default")
      (node (ref "IC3") (pin "8") (pinfunction "PD2(INT2/AIN1/RXD1)_8") (pintype "bidirectional"))
    )
    (net (code "33") (name "/SCART_BLANKING") (class "Default")
      (node (ref "R50") (pin "1") (pinfunction "1_1") (pintype "passive"))
      (node (ref "X2") (pin "16") (pinfunction "16_16") (pintype "passive"))
    )
    (net (code "34") (name "/SCART_BLUE") (class "Default")
      (node (ref "R31") (pin "1") (pinfunction "1_1") (pintype "passive"))
      (node (ref "R32") (pin "1") (pinfunction "1_1") (pintype "passive"))
      (node (ref "R33") (pin "1") (pinfunction "1_1") (pintype "passive"))
      (node (ref "X2") (pin "7") (pinfunction "7_7") (pintype "passive"))
    )
    (net (code "35") (name "/SCART_COMP") (class "Default")
      (node (ref "R13") (pin "1") (pinfunction "1_1") (pintype "passive"))
      (node (ref "R14") (pin "1") (pinfunction "1_1") (pintype "passive"))
      (node (ref "X2") (pin "19") (pinfunction "19_19") (pintype "passive"))
    )
    (net (code "36") (name "/SCART_GREEN") (class "Default")
      (node (ref "R26") (pin "1") (pinfunction "1_1") (pintype "passive"))
      (node (ref "R27") (pin "1") (pinfunction "1_1") (pintype "passive"))
      (node (ref "R28") (pin "1") (pinfunction "1_1") (pintype "passive"))
      (node (ref "X2") (pin "11") (pinfunction "11_11") (pintype "passive"))
    )
    (net (code "37") (name "/SCART_LEFT") (class "Default")
      (node (ref "C3") (pin "2") (pinfunction "2_2") (pintype "passive"))
      (node (ref "X2") (pin "3") (pinfunction "3_3") (pintype "passive"))
    )
    (net (code "38") (name "/SCART_MODE") (class "Default")
      (node (ref "X2") (pin "8") (pinfunction "8_8") (pintype "passive"))
    )
    (net (code "39") (name "/SCART_RED") (class "Default")
      (node (ref "R15") (pin "1") (pinfunction "1_1") (pintype "passive"))
      (node (ref "R16") (pin "1") (pinfunction "1_1") (pintype "passive"))
      (node (ref "R20") (pin "1") (pinfunction "1_1") (pintype "passive"))
      (node (ref "X2") (pin "15") (pinfunction "15_15") (pintype "passive"))
    )
    (net (code "40") (name "/SCART_RIGHT") (class "Default")
      (node (ref "C4") (pin "2") (pinfunction "2_2") (pintype "passive"))
      (node (ref "X2") (pin "1") (pinfunction "1_1") (pintype "passive"))
    )
    (net (code "41") (name "/SPI_MISO") (class "Default")
      (node (ref "IC3") (pin "17") (pinfunction "PB3(PDO/MISO/PCINT3)_17") (pintype "bidirectional"))
    )
    (net (code "42") (name "/SPI_MOSI") (class "Default")
      (node (ref "IC3") (pin "16") (pinfunction "PB2(PDI/MOSI/PCINT2)_16") (pintype "bidirectional"))
    )
    (net (code "43") (name "/SPI_SCLK") (class "Default")
      (node (ref "IC3") (pin "15") (pinfunction "PB1(SCK/PCINT1)_15") (pintype "bidirectional"))
    )
    (net (code "44") (name "/SPI_SEL") (class "Default")
      (node (ref "IC3") (pin "14") (pinfunction "PB0(SS/PCINT0)_14") (pintype "bidirectional"))
    )
    (net (code "45") (name "/TCK") (class "Default")
      (node (ref "IC1") (pin "6") (pinfunction "TCK_6") (pintype "bidirectional"))
      (node (ref "IC3") (pin "18") (pinfunction "PB4(T1/PCINT4)_18") (pintype "bidirectional"))
      (node (ref "JP3") (pin "3") (pinfunction "3_3") (pintype "passive"))
      (node (ref "R2") (pin "2") (pinfunction "2_2") (pintype "passive"))
    )
    (net (code "46") (name "/TDI_FPGA") (class "Default")
      (node (ref "IC3") (pin "20") (pinfunction "PB6(PCINT6)_20") (pintype "bidirectional"))
      (node (ref "R1") (pin "2") (pinfunction "2_2") (pintype "passive"))
    )
    (net (code "47") (name "/TDO_EXP") (class "Default")
      (node (ref "IC3") (pin "21") (pinfunction "PB7(OC0A/OC1C/PCINT7)_21") (pintype "bidirectional"))
      (node (ref "JP3") (pin "1") (pinfunction "1_1") (pintype "passive"))
    )
    (net (code "48") (name "/TDO_PROM") (class "Default")
      (node (ref "IC1") (pin "17") (pinfunction "TDO_17") (pintype "bidirectional"))
      (node (ref "IC3") (pin "22") (pinfunction "PC7(ICP1/INT4/CLKO)_22") (pintype "bidirectional"))
      (node (ref "JP3") (pin "2") (pinfunction "2_2") (pintype "passive"))
    )
    (net (code "49") (name "/TMS") (class "Default")
      (node (ref "IC1") (pin "5") (pinfunction "TMS_5") (pintype "bidirectional"))
      (node (ref "IC3") (pin "19") (pinfunction "PB5(PCINT5)_19") (pintype "bidirectional"))
      (node (ref "JP3") (pin "5") (pinfunction "5_5") (pintype "passive"))
      (node (ref "R3") (pin "2") (pinfunction "2_2") (pintype "passive"))
    )
    (net (code "50") (name "/TXD") (class "Default")
      (node (ref "IC3") (pin "9") (pinfunction "PD3(INT3/TXD1)_9") (pintype "bidirectional"))
    )
    (net (code "51") (name "/VCC") (class "Default")
      (node (ref "C10") (pin "1") (pinfunction "1_1") (pintype "passive"))
      (node (ref "C11") (pin "1") (pinfunction "1_1") (pintype "passive"))
      (node (ref "C12") (pin "1") (pinfunction "1_1") (pintype "passive"))
      (node (ref "C13") (pin "1") (pinfunction "1_1") (pintype "passive"))
      (node (ref "C14") (pin "1") (pinfunction "1_1") (pintype "passive"))
      (node (ref "C15") (pin "1") (pinfunction "1_1") (pintype "passive"))
      (node (ref "C16") (pin "1") (pinfunction "1_1") (pintype "passive"))
      (node (ref "C17") (pin "1") (pinfunction "1_1") (pintype "passive"))
      (node (ref "C26") (pin "1") (pinfunction "1_1") (pintype "passive"))
      (node (ref "C27") (pin "1") (pinfunction "1_1") (pintype "passive"))
      (node (ref "C28") (pin "1") (pinfunction "1_1") (pintype "passive"))
      (node (ref "C29") (pin "1") (pinfunction "1_1") (pintype "passive"))
      (node (ref "C30") (pin "1") (pinfunction "1_1") (pintype "passive"))
      (node (ref "C31") (pin "1") (pinfunction "1_1") (pintype "passive"))
      (node (ref "C32") (pin "1") (pinfunction "1_1") (pintype "passive"))
      (node (ref "C6") (pin "1") (pinfunction "1_1") (pintype "passive"))
      (node (ref "C7") (pin "1") (pinfunction "1_1") (pintype "passive"))
      (node (ref "C8") (pin "1") (pinfunction "1_1") (pintype "passive"))
      (node (ref "C9") (pin "1") (pinfunction "1_1") (pintype "passive"))
      (node (ref "IC1") (pin "18") (pinfunction "VCCINT_18") (pintype "bidirectional"))
      (node (ref "IC1") (pin "19") (pinfunction "VCCO_19") (pintype "bidirectional"))
      (node (ref "IC1") (pin "20") (pinfunction "VCCJ_20") (pintype "bidirectional"))
      (node (ref "IC2") (pin "8") (pinfunction "VCC_8") (pintype "power_in"))
      (node (ref "IC3") (pin "31") (pinfunction "UVCC_31") (pintype "bidirectional"))
      (node (ref "IC3") (pin "32") (pinfunction "AVCC_32") (pintype "bidirectional"))
      (node (ref "IC3") (pin "4") (pinfunction "VCC_4") (pintype "bidirectional"))
      (node (ref "JP3") (pin "4") (pinfunction "4_4") (pintype "passive"))
      (node (ref "Q5") (pin "3") (pinfunction "C_3") (pintype "passive"))
      (node (ref "Q6") (pin "3") (pinfunction "C_3") (pintype "passive"))
      (node (ref "Q7") (pin "3") (pinfunction "C_3") (pintype "passive"))
      (node (ref "Q8") (pin "3") (pinfunction "C_3") (pintype "passive"))
      (node (ref "R22") (pin "1") (pinfunction "1_1") (pintype "passive"))
      (node (ref "R35") (pin "2") (pinfunction "2_2") (pintype "passive"))
      (node (ref "R36") (pin "2") (pinfunction "2_2") (pintype "passive"))
      (node (ref "R37") (pin "2") (pinfunction "2_2") (pintype "passive"))
      (node (ref "R38") (pin "2") (pinfunction "2_2") (pintype "passive"))
      (node (ref "R39") (pin "2") (pinfunction "2_2") (pintype "passive"))
      (node (ref "R4") (pin "2") (pinfunction "2_2") (pintype "passive"))
      (node (ref "R40") (pin "1") (pinfunction "1_1") (pintype "passive"))
      (node (ref "R41") (pin "1") (pinfunction "1_1") (pintype "passive"))
      (node (ref "R42") (pin "1") (pinfunction "1_1") (pintype "passive"))
      (node (ref "R43") (pin "1") (pinfunction "1_1") (pintype "passive"))
      (node (ref "R44") (pin "1") (pinfunction "1_1") (pintype "passive"))
      (node (ref "R45") (pin "1") (pinfunction "1_1") (pintype "passive"))
      (node (ref "R46") (pin "2") (pinfunction "2_2") (pintype "passive"))
      (node (ref "R52") (pin "1") (pinfunction "1_1") (pintype "passive"))
      (node (ref "R6") (pin "2") (pinfunction "2_2") (pintype "passive"))
      (node (ref "T1") (pin "3") (pinfunction "G_3") (pintype "passive"))
      (node (ref "T2") (pin "3") (pinfunction "C_3") (pintype "passive"))
      (node (ref "T3") (pin "3") (pinfunction "G_3") (pintype "passive"))
      (node (ref "U$1") (pin "P8") (pinfunction "VCC_P8") (pintype "bidirectional"))
      (node (ref "U$2") (pin "VDD") (pinfunction "VDD_VDD") (pintype "power_in"))
      (node (ref "U$4") (pin "4") (pinfunction "VOUT1_4") (pintype "bidirectional"))
      (node (ref "U1") (pin "P106") (pinfunction "VCCO_RIGHT2_P106") (pintype "passive"))
      (node (ref "U1") (pin "P115") (pinfunction "VCCO_TOP0_P115") (pintype "passive"))
      (node (ref "U1") (pin "P126") (pinfunction "VCCO_TOP1_P126") (pintype "passive"))
      (node (ref "U1") (pin "P138") (pinfunction "VCCO_TOP2_P138") (pintype "passive"))
      (node (ref "U1") (pin "P19") (pinfunction "VCCO_LEFT1_P19") (pintype "passive"))
      (node (ref "U1") (pin "P3") (pinfunction "VCCO_LEFT0_P3") (pintype "passive"))
      (node (ref "U1") (pin "P34") (pinfunction "VCCO_LEFT2_P34") (pintype "passive"))
      (node (ref "U1") (pin "P43") (pinfunction "VCCO_BOTTOM0_P43") (pintype "passive"))
      (node (ref "U1") (pin "P54") (pinfunction "VCCO_BOTTOM1_P54") (pintype "passive"))
      (node (ref "U1") (pin "P66") (pinfunction "VCCO_BOTTOM2_P66") (pintype "passive"))
      (node (ref "U1") (pin "P75") (pinfunction "VCCO_RIGHT0_P75") (pintype "passive"))
      (node (ref "U1") (pin "P91") (pinfunction "VCCO_RIGHT1_P91") (pintype "passive"))
    )
    (net (code "52") (name "/VCC5") (class "Default")
      (node (ref "C33") (pin "+") (pinfunction "+_+") (pintype "passive"))
      (node (ref "R5") (pin "2") (pinfunction "2_2") (pintype "passive"))
      (node (ref "R7") (pin "2") (pinfunction "2_2") (pintype "passive"))
      (node (ref "REG1.2") (pin "3") (pinfunction "VCC_3") (pintype "bidirectional"))
      (node (ref "REG2.5") (pin "3") (pinfunction "VCC_3") (pintype "bidirectional"))
      (node (ref "U$4") (pin "3") (pinfunction "VCC_3") (pintype "bidirectional"))
      (node (ref "X3") (pin "5") (pinfunction "5_5") (pintype "passive"))
      (node (ref "X8") (pin "2") (pinfunction "2_2") (pintype "power_in"))
    )
    (net (code "53") (name "/VCCAUX") (class "Default")
      (node (ref "C18") (pin "1") (pinfunction "1_1") (pintype "passive"))
      (node (ref "C19") (pin "1") (pinfunction "1_1") (pintype "passive"))
      (node (ref "C20") (pin "1") (pinfunction "1_1") (pintype "passive"))
      (node (ref "C21") (pin "1") (pinfunction "1_1") (pintype "passive"))
      (node (ref "R50") (pin "2") (pinfunction "2_2") (pintype "passive"))
      (node (ref "REG2.5") (pin "4") (pinfunction "VOUT1_4") (pintype "bidirectional"))
      (node (ref "U1") (pin "P120") (pinfunction "VCCAUX2_P120") (pintype "passive"))
      (node (ref "U1") (pin "P134") (pinfunction "VCCAUX3_P134") (pintype "passive"))
      (node (ref "U1") (pin "P48") (pinfunction "VCCAUX0_P48") (pintype "passive"))
      (node (ref "U1") (pin "P62") (pinfunction "VCCAUX1_P62") (pintype "passive"))
    )
    (net (code "54") (name "/VCCINT") (class "Default")
      (node (ref "C22") (pin "1") (pinfunction "1_1") (pintype "passive"))
      (node (ref "C23") (pin "1") (pinfunction "1_1") (pintype "passive"))
      (node (ref "C24") (pin "1") (pinfunction "1_1") (pintype "passive"))
      (node (ref "C25") (pin "1") (pinfunction "1_1") (pintype "passive"))
      (node (ref "REG1.2") (pin "4") (pinfunction "VOUT1_4") (pintype "bidirectional"))
      (node (ref "U1") (pin "P121") (pinfunction "VCCINT2_P121") (pintype "passive"))
      (node (ref "U1") (pin "P133") (pinfunction "VCCINT3_P133") (pintype "passive"))
      (node (ref "U1") (pin "P49") (pinfunction "VCCINT0_P49") (pintype "passive"))
      (node (ref "U1") (pin "P61") (pinfunction "VCCINT1_P61") (pintype "passive"))
    )
    (net (code "55") (name "/VCC_B3") (class "Default")
      (node (ref "R11") (pin "2") (pinfunction "2_2") (pintype "passive"))
    )
    (net (code "56") (name "/X6") (class "Default")
      (node (ref "U1") (pin "P51") (pinfunction "IO_L31N_5D4_P51") (pintype "bidirectional"))
    )
    (net (code "59") (name "/XXCSYNC") (class "Default")
      (node (ref "U1") (pin "P137") (pinfunction "IO_L27N_0_P137") (pintype "bidirectional"))
    )
    (net (code "61") (name "/XXR0") (class "Default")
      (node (ref "U1") (pin "P140") (pinfunction "IO_L01P_0VRN_0_P140") (pintype "bidirectional"))
    )
    (net (code "62") (name "/XXR1") (class "Default")
      (node (ref "U1") (pin "P141") (pinfunction "IO_L01N_0VRP_0_P141") (pintype "bidirectional"))
    )
    (net (code "63") (name "GND") (class "Default")
      (node (ref "C1") (pin "1") (pinfunction "1_1") (pintype "passive"))
      (node (ref "C10") (pin "2") (pinfunction "2_2") (pintype "passive"))
      (node (ref "C11") (pin "2") (pinfunction "2_2") (pintype "passive"))
      (node (ref "C12") (pin "2") (pinfunction "2_2") (pintype "passive"))
      (node (ref "C13") (pin "2") (pinfunction "2_2") (pintype "passive"))
      (node (ref "C14") (pin "2") (pinfunction "2_2") (pintype "passive"))
      (node (ref "C15") (pin "2") (pinfunction "2_2") (pintype "passive"))
      (node (ref "C16") (pin "2") (pinfunction "2_2") (pintype "passive"))
      (node (ref "C17") (pin "2") (pinfunction "2_2") (pintype "passive"))
      (node (ref "C18") (pin "2") (pinfunction "2_2") (pintype "passive"))
      (node (ref "C19") (pin "2") (pinfunction "2_2") (pintype "passive"))
      (node (ref "C20") (pin "2") (pinfunction "2_2") (pintype "passive"))
      (node (ref "C21") (pin "2") (pinfunction "2_2") (pintype "passive"))
      (node (ref "C22") (pin "2") (pinfunction "2_2") (pintype "passive"))
      (node (ref "C23") (pin "2") (pinfunction "2_2") (pintype "passive"))
      (node (ref "C24") (pin "2") (pinfunction "2_2") (pintype "passive"))
      (node (ref "C25") (pin "2") (pinfunction "2_2") (pintype "passive"))
      (node (ref "C26") (pin "2") (pinfunction "2_2") (pintype "passive"))
      (node (ref "C27") (pin "2") (pinfunction "2_2") (pintype "passive"))
      (node (ref "C28") (pin "2") (pinfunction "2_2") (pintype "passive"))
      (node (ref "C29") (pin "2") (pinfunction "2_2") (pintype "passive"))
      (node (ref "C30") (pin "2") (pinfunction "2_2") (pintype "passive"))
      (node (ref "C31") (pin "2") (pinfunction "2_2") (pintype "passive"))
      (node (ref "C32") (pin "2") (pinfunction "2_2") (pintype "passive"))
      (node (ref "C33") (pin "-") (pinfunction "-_-") (pintype "passive"))
      (node (ref "C5") (pin "1") (pinfunction "1_1") (pintype "passive"))
      (node (ref "C6") (pin "2") (pinfunction "2_2") (pintype "passive"))
      (node (ref "C7") (pin "2") (pinfunction "2_2") (pintype "passive"))
      (node (ref "C8") (pin "2") (pinfunction "2_2") (pintype "passive"))
      (node (ref "C9") (pin "2") (pinfunction "2_2") (pintype "passive"))
      (node (ref "IC1") (pin "11") (pinfunction "GND_11") (pintype "bidirectional"))
      (node (ref "IC2") (pin "4") (pinfunction "GND_4") (pintype "power_in"))
      (node (ref "IC3") (pin "3") (pinfunction "GND_3") (pintype "bidirectional"))
      (node (ref "JP3") (pin "6") (pinfunction "6_6") (pintype "passive"))
      (node (ref "R12") (pin "1") (pinfunction "1_1") (pintype "passive"))
      (node (ref "R17") (pin "1") (pinfunction "1_1") (pintype "passive"))
      (node (ref "R19") (pin "1") (pinfunction "1_1") (pintype "passive"))
      (node (ref "R21") (pin "1") (pinfunction "1_1") (pintype "passive"))
      (node (ref "REG1.2") (pin "1") (pinfunction "GND_1") (pintype "bidirectional"))
      (node (ref "REG2.5") (pin "1") (pinfunction "GND_1") (pintype "bidirectional"))
      (node (ref "RESET_SW") (pin "2") (pinfunction "2_2") (pintype "passive"))
      (node (ref "U$1") (pin "P24") (pinfunction "VSS_P24") (pintype "bidirectional"))
      (node (ref "U$1") (pin "P30") (pinfunction "CE_P30") (pintype "bidirectional"))
      (node (ref "U$2") (pin "GND") (pinfunction "GND_GND") (pintype "power_in"))
      (node (ref "U$4") (pin "1") (pinfunction "GND_1") (pintype "bidirectional"))
      (node (ref "U1") (pin "P101") (pinfunction "GND11_P101") (pintype "passive"))
      (node (ref "U1") (pin "P114") (pinfunction "GND12_P114") (pintype "passive"))
      (node (ref "U1") (pin "P117") (pinfunction "GND13_P117") (pintype "passive"))
      (node (ref "U1") (pin "P136") (pinfunction "GND14_P136") (pintype "passive"))
      (node (ref "U1") (pin "P139") (pinfunction "GND15_P139") (pintype "passive"))
      (node (ref "U1") (pin "P16") (pinfunction "GND1_P16") (pintype "passive"))
      (node (ref "U1") (pin "P22") (pinfunction "GND2_P22") (pintype "passive"))
      (node (ref "U1") (pin "P29") (pinfunction "GND3_P29") (pintype "passive"))
      (node (ref "U1") (pin "P37") (pinfunction "M1_P37") (pintype "bidirectional"))
      (node (ref "U1") (pin "P38") (pinfunction "M0_P38") (pintype "bidirectional"))
      (node (ref "U1") (pin "P39") (pinfunction "M2_P39") (pintype "bidirectional"))
      (node (ref "U1") (pin "P42") (pinfunction "GND4_P42") (pintype "passive"))
      (node (ref "U1") (pin "P45") (pinfunction "GND5_P45") (pintype "passive"))
      (node (ref "U1") (pin "P64") (pinfunction "GND6_P64") (pintype "passive"))
      (node (ref "U1") (pin "P67") (pinfunction "GND7_P67") (pintype "passive"))
      (node (ref "U1") (pin "P81") (pinfunction "GND8_P81") (pintype "passive"))
      (node (ref "U1") (pin "P88") (pinfunction "GND9_P88") (pintype "passive"))
      (node (ref "U1") (pin "P9") (pinfunction "GND0_P9") (pintype "passive"))
      (node (ref "U1") (pin "P94") (pinfunction "GND10_P94") (pintype "passive"))
      (node (ref "X1") (pin "3") (pinfunction "2_3") (pintype "passive"))
      (node (ref "X2") (pin "13") (pinfunction "13_13") (pintype "passive"))
      (node (ref "X2") (pin "14") (pinfunction "14_14") (pintype "passive"))
      (node (ref "X2") (pin "17") (pinfunction "17_17") (pintype "passive"))
      (node (ref "X2") (pin "18") (pinfunction "18_18") (pintype "passive"))
      (node (ref "X2") (pin "21") (pinfunction "21_21") (pintype "passive"))
      (node (ref "X2") (pin "4") (pinfunction "4_4") (pintype "passive"))
      (node (ref "X2") (pin "5") (pinfunction "5_5") (pintype "passive"))
      (node (ref "X2") (pin "9") (pinfunction "9_9") (pintype "passive"))
      (node (ref "X3") (pin "3") (pinfunction "3_3") (pintype "passive"))
      (node (ref "X3") (pin "SH2") (pinfunction "PE2_SH2") (pintype "power_in"))
      (node (ref "X4") (pin "8") (pinfunction "F_8") (pintype "passive"))
      (node (ref "X4") (pin "G1") (pinfunction "G1_G1") (pintype "passive"))
      (node (ref "X5") (pin "8") (pinfunction "F_8") (pintype "passive"))
      (node (ref "X5") (pin "G1") (pinfunction "G1_G1") (pintype "passive"))
      (node (ref "X8") (pin "1") (pinfunction "1_1") (pintype "power_in"))
      (node (ref "X8") (pin "3") (pinfunction "3_3") (pintype "power_in"))
    )
    (net (code "64") (name "Net-(C1-Pad2)") (class "Default")
      (node (ref "C1") (pin "2") (pinfunction "2_2") (pintype "passive"))
      (node (ref "R23") (pin "2") (pinfunction "2_2") (pintype "passive"))
      (node (ref "R48") (pin "1") (pinfunction "1_1") (pintype "passive"))
    )
    (net (code "65") (name "Net-(C2-Pad1)") (class "Default")
      (node (ref "C2") (pin "1") (pinfunction "1_1") (pintype "passive"))
      (node (ref "R17") (pin "2") (pinfunction "2_2") (pintype "passive"))
      (node (ref "X1") (pin "1") (pinfunction "1_1") (pintype "passive"))
    )
    (net (code "66") (name "Net-(C3-Pad1)") (class "Default")
      (node (ref "C3") (pin "1") (pinfunction "1_1") (pintype "passive"))
      (node (ref "R48") (pin "2") (pinfunction "2_2") (pintype "passive"))
    )
    (net (code "67") (name "Net-(C4-Pad1)") (class "Default")
      (node (ref "C4") (pin "1") (pinfunction "1_1") (pintype "passive"))
      (node (ref "R49") (pin "2") (pinfunction "2_2") (pintype "passive"))
    )
    (net (code "68") (name "Net-(C5-Pad2)") (class "Default")
      (node (ref "C5") (pin "2") (pinfunction "2_2") (pintype "passive"))
      (node (ref "R34") (pin "2") (pinfunction "2_2") (pintype "passive"))
      (node (ref "R49") (pin "1") (pinfunction "1_1") (pintype "passive"))
    )
    (net (code "69") (name "Net-(IC1-CLK)") (class "Default")
      (node (ref "IC1") (pin "3") (pinfunction "CLK_3") (pintype "bidirectional"))
      (node (ref "U1") (pin "P72") (pinfunction "CCLK_P72") (pintype "bidirectional"))
    )
    (net (code "70") (name "Net-(IC1-TDI)") (class "Default")
      (node (ref "IC1") (pin "4") (pinfunction "TDI_4") (pintype "bidirectional"))
      (node (ref "U1") (pin "P109") (pinfunction "TDO_P109") (pintype "bidirectional"))
    )
    (net (code "71") (name "Net-(IC1-{slash}CE)") (class "Default")
      (node (ref "IC1") (pin "10") (pinfunction "/CE_10") (pintype "bidirectional"))
      (node (ref "U1") (pin "P71") (pinfunction "DONE_P71") (pintype "bidirectional"))
    )
    (net (code "72") (name "Net-(IC1-{slash}CF)") (class "Default")
      (node (ref "IC1") (pin "7") (pinfunction "/CF_7") (pintype "bidirectional"))
      (node (ref "U1") (pin "P143") (pinfunction "PROG_B_P143") (pintype "bidirectional"))
    )
    (net (code "73") (name "Net-(IC3-D+)") (class "Default")
      (node (ref "IC3") (pin "29") (pinfunction "D+_29") (pintype "bidirectional"))
      (node (ref "R54") (pin "2") (pinfunction "2_2") (pintype "passive"))
    )
    (net (code "74") (name "Net-(IC3-D-)") (class "Default")
      (node (ref "IC3") (pin "30") (pinfunction "D-_30") (pintype "bidirectional"))
      (node (ref "R53") (pin "2") (pinfunction "2_2") (pintype "passive"))
    )
    (net (code "75") (name "Net-(IC3-UGND)") (class "Default")
      (node (ref "IC3") (pin "28") (pinfunction "UGND_28") (pintype "bidirectional"))
      (node (ref "X6") (pin "4") (pinfunction "4_4") (pintype "passive"))
    )
    (net (code "76") (name "Net-(Q5-B)") (class "Default")
      (node (ref "Q5") (pin "1") (pinfunction "B_1") (pintype "passive"))
      (node (ref "R8") (pin "2") (pinfunction "2_2") (pintype "passive"))
    )
    (net (code "77") (name "Net-(Q5-E)") (class "Default")
      (node (ref "Q5") (pin "2") (pinfunction "E_2") (pintype "passive"))
      (node (ref "R13") (pin "2") (pinfunction "2_2") (pintype "passive"))
      (node (ref "R14") (pin "2") (pinfunction "2_2") (pintype "passive"))
    )
    (net (code "78") (name "Net-(Q6-B)") (class "Default")
      (node (ref "Q6") (pin "1") (pinfunction "B_1") (pintype "passive"))
      (node (ref "R10") (pin "2") (pinfunction "2_2") (pintype "passive"))
      (node (ref "R9") (pin "2") (pinfunction "2_2") (pintype "passive"))
    )
    (net (code "79") (name "Net-(Q6-E)") (class "Default")
      (node (ref "Q6") (pin "2") (pinfunction "E_2") (pintype "passive"))
      (node (ref "R15") (pin "2") (pinfunction "2_2") (pintype "passive"))
      (node (ref "R16") (pin "2") (pinfunction "2_2") (pintype "passive"))
      (node (ref "R20") (pin "2") (pinfunction "2_2") (pintype "passive"))
    )
    (net (code "80") (name "Net-(Q7-B)") (class "Default")
      (node (ref "Q7") (pin "1") (pinfunction "B_1") (pintype "passive"))
      (node (ref "R29") (pin "2") (pinfunction "2_2") (pintype "passive"))
      (node (ref "R30") (pin "2") (pinfunction "2_2") (pintype "passive"))
    )
    (net (code "81") (name "Net-(Q7-E)") (class "Default")
      (node (ref "Q7") (pin "2") (pinfunction "E_2") (pintype "passive"))
      (node (ref "R31") (pin "2") (pinfunction "2_2") (pintype "passive"))
      (node (ref "R32") (pin "2") (pinfunction "2_2") (pintype "passive"))
      (node (ref "R33") (pin "2") (pinfunction "2_2") (pintype "passive"))
    )
    (net (code "82") (name "Net-(Q8-B)") (class "Default")
      (node (ref "Q8") (pin "1") (pinfunction "B_1") (pintype "passive"))
      (node (ref "R24") (pin "2") (pinfunction "2_2") (pintype "passive"))
      (node (ref "R25") (pin "2") (pinfunction "2_2") (pintype "passive"))
    )
    (net (code "83") (name "Net-(Q8-E)") (class "Default")
      (node (ref "Q8") (pin "2") (pinfunction "E_2") (pintype "passive"))
      (node (ref "R26") (pin "2") (pinfunction "2_2") (pintype "passive"))
      (node (ref "R27") (pin "2") (pinfunction "2_2") (pintype "passive"))
      (node (ref "R28") (pin "2") (pinfunction "2_2") (pintype "passive"))
    )
    (net (code "84") (name "Net-(R18-Pad2)") (class "Default")
      (node (ref "R18") (pin "2") (pinfunction "2_2") (pintype "passive"))
      (node (ref "R22") (pin "2") (pinfunction "2_2") (pintype "passive"))
    )
    (net (code "85") (name "Net-(R53-Pad1)") (class "Default")
      (node (ref "R53") (pin "1") (pinfunction "1_1") (pintype "passive"))
      (node (ref "X6") (pin "2") (pinfunction "2_2") (pintype "passive"))
    )
    (net (code "86") (name "Net-(R54-Pad1)") (class "Default")
      (node (ref "R54") (pin "1") (pinfunction "1_1") (pintype "passive"))
      (node (ref "X6") (pin "3") (pinfunction "3_3") (pintype "passive"))
    )
    (net (code "87") (name "Net-(T2-B)") (class "Default")
      (node (ref "C2") (pin "2") (pinfunction "2_2") (pintype "passive"))
      (node (ref "R18") (pin "1") (pinfunction "1_1") (pintype "passive"))
      (node (ref "R19") (pin "2") (pinfunction "2_2") (pintype "passive"))
      (node (ref "T2") (pin "1") (pinfunction "B_1") (pintype "passive"))
    )
    (net (code "88") (name "Net-(U$1-A0)") (class "Default")
      (node (ref "U$1") (pin "P20") (pinfunction "A0_P20") (pintype "bidirectional"))
      (node (ref "U1") (pin "P77") (pinfunction "IO_L20P_3_P77") (pintype "bidirectional"))
    )
    (net (code "89") (name "Net-(U$1-A1)") (class "Default")
      (node (ref "U$1") (pin "P19") (pinfunction "A1_P19") (pintype "bidirectional"))
      (node (ref "U1") (pin "P76") (pinfunction "IO_P76") (pintype "bidirectional"))
    )
    (net (code "90") (name "Net-(U$1-A2)") (class "Default")
      (node (ref "U$1") (pin "P18") (pinfunction "A2_P18") (pintype "bidirectional"))
      (node (ref "U1") (pin "P74") (pinfunction "IO_L01N_3VRP_3_P74") (pintype "bidirectional"))
    )
    (net (code "91") (name "Net-(U$1-A3)") (class "Default")
      (node (ref "U$1") (pin "P17") (pinfunction "A3_P17") (pintype "bidirectional"))
      (node (ref "U1") (pin "P73") (pinfunction "IO_L01P_3VRN_3_P73") (pintype "bidirectional"))
    )
    (net (code "92") (name "Net-(U$1-A4)") (class "Default")
      (node (ref "U$1") (pin "P16") (pinfunction "A4_P16") (pintype "bidirectional"))
      (node (ref "U1") (pin "P108") (pinfunction "IO_L01N_2VRP_2_P108") (pintype "bidirectional"))
    )
    (net (code "93") (name "Net-(U$1-A5)") (class "Default")
      (node (ref "U$1") (pin "P15") (pinfunction "A5_P15") (pintype "bidirectional"))
      (node (ref "U1") (pin "P107") (pinfunction "IO_L01P_2VRN_2_P107") (pintype "bidirectional"))
    )
    (net (code "94") (name "Net-(U$1-A6)") (class "Default")
      (node (ref "U$1") (pin "P14") (pinfunction "A6_P14") (pintype "bidirectional"))
      (node (ref "U1") (pin "P105") (pinfunction "IO_L20N_2_P105") (pintype "bidirectional"))
    )
    (net (code "95") (name "Net-(U$1-A7)") (class "Default")
      (node (ref "U$1") (pin "P13") (pinfunction "A7_P13") (pintype "bidirectional"))
      (node (ref "U1") (pin "P104") (pinfunction "IO_L20P_2_P104") (pintype "bidirectional"))
    )
    (net (code "96") (name "Net-(U$1-A8)") (class "Default")
      (node (ref "U$1") (pin "P3") (pinfunction "A8_P3") (pintype "bidirectional"))
      (node (ref "U1") (pin "P93") (pinfunction "IO_L40N_2_P93") (pintype "bidirectional"))
    )
    (net (code "97") (name "Net-(U$1-A9)") (class "Default")
      (node (ref "U$1") (pin "P2") (pinfunction "A9_P2") (pintype "bidirectional"))
      (node (ref "U1") (pin "P92") (pinfunction "IO_L40P_2VREF_2_P92") (pintype "bidirectional"))
    )
    (net (code "98") (name "Net-(U$1-A10)") (class "Default")
      (node (ref "U$1") (pin "P31") (pinfunction "A10_P31") (pintype "bidirectional"))
      (node (ref "U1") (pin "P87") (pinfunction "IO_L24N_3_P87") (pintype "bidirectional"))
    )
    (net (code "99") (name "Net-(U$1-A11)") (class "Default")
      (node (ref "U$1") (pin "P1") (pinfunction "A11_P1") (pintype "bidirectional"))
      (node (ref "U1") (pin "P90") (pinfunction "IO_L40N_3VREF_3_P90") (pintype "bidirectional"))
    )
    (net (code "100") (name "Net-(U$1-A12)") (class "Default")
      (node (ref "U$1") (pin "P12") (pinfunction "A12_P12") (pintype "bidirectional"))
      (node (ref "U1") (pin "P103") (pinfunction "IO_L21N_2_P103") (pintype "bidirectional"))
    )
    (net (code "101") (name "Net-(U$1-A13)") (class "Default")
      (node (ref "U$1") (pin "P4") (pinfunction "A13_P4") (pintype "bidirectional"))
      (node (ref "U1") (pin "P95") (pinfunction "IO_L24P_2_P95") (pintype "bidirectional"))
    )
    (net (code "102") (name "Net-(U$1-A14)") (class "Default")
      (node (ref "U$1") (pin "P11") (pinfunction "A14_P11") (pintype "bidirectional"))
      (node (ref "U1") (pin "P102") (pinfunction "IO_L21P_2_P102") (pintype "bidirectional"))
    )
    (net (code "103") (name "Net-(U$1-A15)") (class "Default")
      (node (ref "U$1") (pin "P7") (pinfunction "A15_P7") (pintype "bidirectional"))
      (node (ref "U1") (pin "P98") (pinfunction "IO_L23N_2VREF_2_P98") (pintype "bidirectional"))
    )
    (net (code "104") (name "Net-(U$1-A16)") (class "Default")
      (node (ref "U$1") (pin "P10") (pinfunction "A16_P10") (pintype "bidirectional"))
      (node (ref "U1") (pin "P100") (pinfunction "IO_L22N_2_P100") (pintype "bidirectional"))
    )
    (net (code "105") (name "Net-(U$1-A17)") (class "Default")
      (node (ref "U$1") (pin "P6") (pinfunction "A17_P6") (pintype "bidirectional"))
      (node (ref "U1") (pin "P97") (pinfunction "IO_L23P_2_P97") (pintype "bidirectional"))
    )
    (net (code "106") (name "Net-(U$1-A18)") (class "Default")
      (node (ref "U$1") (pin "P9") (pinfunction "A18_P9") (pintype "bidirectional"))
      (node (ref "U1") (pin "P99") (pinfunction "IO_L22P_2_P99") (pintype "bidirectional"))
    )
    (net (code "107") (name "Net-(U$1-DQ0)") (class "Default")
      (node (ref "U$1") (pin "P21") (pinfunction "DQ0_P21") (pintype "bidirectional"))
      (node (ref "U1") (pin "P78") (pinfunction "IO_L20N_3_P78") (pintype "bidirectional"))
    )
    (net (code "108") (name "Net-(U$1-DQ1)") (class "Default")
      (node (ref "U$1") (pin "P22") (pinfunction "DQ1_P22") (pintype "bidirectional"))
      (node (ref "U1") (pin "P79") (pinfunction "IO_L21P_3_P79") (pintype "bidirectional"))
    )
    (net (code "109") (name "Net-(U$1-DQ2)") (class "Default")
      (node (ref "U$1") (pin "P23") (pinfunction "DQ2_P23") (pintype "bidirectional"))
      (node (ref "U1") (pin "P80") (pinfunction "IO_L21N_3_P80") (pintype "bidirectional"))
    )
    (net (code "110") (name "Net-(U$1-DQ3)") (class "Default")
      (node (ref "U$1") (pin "P25") (pinfunction "DQ3_P25") (pintype "bidirectional"))
      (node (ref "U1") (pin "P82") (pinfunction "IO_L22P_3_P82") (pintype "bidirectional"))
    )
    (net (code "111") (name "Net-(U$1-DQ4)") (class "Default")
      (node (ref "U$1") (pin "P26") (pinfunction "DQ4_P26") (pintype "bidirectional"))
      (node (ref "U1") (pin "P83") (pinfunction "IO_L22N_3_P83") (pintype "bidirectional"))
    )
    (net (code "112") (name "Net-(U$1-DQ5)") (class "Default")
      (node (ref "U$1") (pin "P27") (pinfunction "DQ5_P27") (pintype "bidirectional"))
      (node (ref "U1") (pin "P84") (pinfunction "IO_L23P_3VREF_3_P84") (pintype "bidirectional"))
    )
    (net (code "113") (name "Net-(U$1-DQ6)") (class "Default")
      (node (ref "U$1") (pin "P28") (pinfunction "DQ6_P28") (pintype "bidirectional"))
      (node (ref "U1") (pin "P85") (pinfunction "IO_L23N_3_P85") (pintype "bidirectional"))
    )
    (net (code "114") (name "Net-(U$1-DQ7)") (class "Default")
      (node (ref "U$1") (pin "P29") (pinfunction "DQ7_P29") (pintype "bidirectional"))
      (node (ref "U1") (pin "P86") (pinfunction "IO_L24P_3_P86") (pintype "bidirectional"))
    )
    (net (code "115") (name "Net-(U$1-OE)") (class "Default")
      (node (ref "U$1") (pin "P32") (pinfunction "OE_P32") (pintype "bidirectional"))
      (node (ref "U1") (pin "P89") (pinfunction "IO_L40P_3_P89") (pintype "bidirectional"))
    )
    (net (code "116") (name "Net-(U$1-WE)") (class "Default")
      (node (ref "U$1") (pin "P5") (pinfunction "WE_P5") (pintype "bidirectional"))
      (node (ref "U1") (pin "P96") (pinfunction "IO_L24N_2_P96") (pintype "bidirectional"))
    )
    (net (code "117") (name "Net-(U1N-TCK)") (class "Default")
      (node (ref "R2") (pin "1") (pinfunction "1_1") (pintype "passive"))
      (node (ref "U1") (pin "P110") (pinfunction "TCK_P110") (pintype "bidirectional"))
    )
    (net (code "118") (name "Net-(U1N-TDI)") (class "Default")
      (node (ref "R1") (pin "1") (pinfunction "1_1") (pintype "passive"))
      (node (ref "U1") (pin "P144") (pinfunction "TDI_P144") (pintype "bidirectional"))
    )
    (net (code "119") (name "Net-(U1N-TMS)") (class "Default")
      (node (ref "R3") (pin "1") (pinfunction "1_1") (pintype "passive"))
      (node (ref "U1") (pin "P111") (pinfunction "TMS_P111") (pintype "bidirectional"))
    )
    (net (code "120") (name "Net-(X4A-F)") (class "Default")
      (node (ref "R40") (pin "2") (pinfunction "2_2") (pintype "passive"))
      (node (ref "X4") (pin "1") (pinfunction "F_1") (pintype "passive"))
    )
    (net (code "121") (name "Net-(X4B-F)") (class "Default")
      (node (ref "R41") (pin "2") (pinfunction "2_2") (pintype "passive"))
      (node (ref "X4") (pin "2") (pinfunction "F_2") (pintype "passive"))
    )
    (net (code "122") (name "Net-(X4C-F)") (class "Default")
      (node (ref "R42") (pin "2") (pinfunction "2_2") (pintype "passive"))
      (node (ref "X4") (pin "3") (pinfunction "F_3") (pintype "passive"))
    )
    (net (code "123") (name "Net-(X4D-F)") (class "Default")
      (node (ref "R43") (pin "2") (pinfunction "2_2") (pintype "passive"))
      (node (ref "X4") (pin "4") (pinfunction "F_4") (pintype "passive"))
    )
    (net (code "124") (name "Net-(X4F-F)") (class "Default")
      (node (ref "R44") (pin "2") (pinfunction "2_2") (pintype "passive"))
      (node (ref "X4") (pin "6") (pinfunction "F_6") (pintype "passive"))
    )
    (net (code "125") (name "Net-(X4G-F)") (class "Default")
      (node (ref "R45") (pin "2") (pinfunction "2_2") (pintype "passive"))
      (node (ref "X4") (pin "7") (pinfunction "F_7") (pintype "passive"))
    )
    (net (code "126") (name "Net-(X5A-F)") (class "Default")
      (node (ref "R46") (pin "1") (pinfunction "1_1") (pintype "passive"))
      (node (ref "X5") (pin "1") (pinfunction "F_1") (pintype "passive"))
    )
    (net (code "127") (name "Net-(X5B-F)") (class "Default")
      (node (ref "R39") (pin "1") (pinfunction "1_1") (pintype "passive"))
      (node (ref "X5") (pin "2") (pinfunction "F_2") (pintype "passive"))
    )
    (net (code "128") (name "Net-(X5C-F)") (class "Default")
      (node (ref "R38") (pin "1") (pinfunction "1_1") (pintype "passive"))
      (node (ref "X5") (pin "3") (pinfunction "F_3") (pintype "passive"))
    )
    (net (code "129") (name "Net-(X5D-F)") (class "Default")
      (node (ref "R37") (pin "1") (pinfunction "1_1") (pintype "passive"))
      (node (ref "X5") (pin "4") (pinfunction "F_4") (pintype "passive"))
    )
    (net (code "130") (name "Net-(X5F-F)") (class "Default")
      (node (ref "R36") (pin "1") (pinfunction "1_1") (pintype "passive"))
      (node (ref "X5") (pin "6") (pinfunction "F_6") (pintype "passive"))
    )
    (net (code "131") (name "Net-(X5G-F)") (class "Default")
      (node (ref "R35") (pin "1") (pinfunction "1_1") (pintype "passive"))
      (node (ref "X5") (pin "7") (pinfunction "F_7") (pintype "passive"))
    )
    (net (code "132") (name "unconnected-(IC1-NC.1-Pad2)") (class "Default")
      (node (ref "IC1") (pin "2") (pinfunction "NC.1_2") (pintype "bidirectional"))
    )
    (net (code "133") (name "unconnected-(IC1-NC.2-Pad9)") (class "Default")
      (node (ref "IC1") (pin "9") (pinfunction "NC.2_9") (pintype "bidirectional"))
    )
    (net (code "134") (name "unconnected-(IC1-NC.3-Pad12)") (class "Default")
      (node (ref "IC1") (pin "12") (pinfunction "NC.3_12") (pintype "bidirectional"))
    )
    (net (code "135") (name "unconnected-(IC1-NC.4-Pad14)") (class "Default")
      (node (ref "IC1") (pin "14") (pinfunction "NC.4_14") (pintype "bidirectional"))
    )
    (net (code "136") (name "unconnected-(IC1-NC.5-Pad15)") (class "Default")
      (node (ref "IC1") (pin "15") (pinfunction "NC.5_15") (pintype "bidirectional"))
    )
    (net (code "137") (name "unconnected-(IC1-NC.6-Pad16)") (class "Default")
      (node (ref "IC1") (pin "16") (pinfunction "NC.6_16") (pintype "bidirectional"))
    )
    (net (code "138") (name "unconnected-(IC1-{slash}CEO-Pad13)") (class "Default")
      (node (ref "IC1") (pin "13") (pinfunction "/CEO_13") (pintype "bidirectional"))
    )
    (net (code "139") (name "unconnected-(IC3-PC2(AIN2{slash}PCIN11)-Pad5)") (class "Default")
      (node (ref "IC3") (pin "5") (pinfunction "PC2(AIN2/PCIN11)_5") (pintype "bidirectional"))
    )
    (net (code "140") (name "unconnected-(IC3-PC4(PCINT10)-Pad26)") (class "Default")
      (node (ref "IC3") (pin "26") (pinfunction "PC4(PCINT10)_26") (pintype "bidirectional"))
    )
    (net (code "141") (name "unconnected-(IC3-PC5(OC1B{slash}PCINT9)-Pad25)") (class "Default")
      (node (ref "IC3") (pin "25") (pinfunction "PC5(OC1B/PCINT9)_25") (pintype "bidirectional"))
    )
    (net (code "142") (name "unconnected-(IC3-PC6(OC1A{slash}PCINT8)-Pad23)") (class "Default")
      (node (ref "IC3") (pin "23") (pinfunction "PC6(OC1A/PCINT8)_23") (pintype "bidirectional"))
    )
    (net (code "143") (name "unconnected-(IC3-PD0(INT0{slash}OC0B)-Pad6)") (class "Default")
      (node (ref "IC3") (pin "6") (pinfunction "PD0(INT0/OC0B)_6") (pintype "bidirectional"))
    )
    (net (code "144") (name "unconnected-(IC3-PD1(INT1{slash}AIN0)-Pad7)") (class "Default")
      (node (ref "IC3") (pin "7") (pinfunction "PD1(INT1/AIN0)_7") (pintype "bidirectional"))
    )
    (net (code "145") (name "unconnected-(IC3-PD4(INT5{slash}AIN3)-Pad10)") (class "Default")
      (node (ref "IC3") (pin "10") (pinfunction "PD4(INT5/AIN3)_10") (pintype "bidirectional"))
    )
    (net (code "146") (name "unconnected-(IC3-PD5(XCK{slash}AIN4{slash}PCINT12)-Pad11)") (class "Default")
      (node (ref "IC3") (pin "11") (pinfunction "PD5(XCK/AIN4/PCINT12)_11") (pintype "bidirectional"))
    )
    (net (code "147") (name "unconnected-(IC3-PD6(INT6{slash}AIN5{slash}RTS)-Pad12)") (class "Default")
      (node (ref "IC3") (pin "12") (pinfunction "PD6(INT6/AIN5/RTS)_12") (pintype "bidirectional"))
    )
    (net (code "148") (name "unconnected-(IC3-UCAP-Pad27)") (class "Default")
      (node (ref "IC3") (pin "27") (pinfunction "UCAP_27") (pintype "bidirectional"))
    )
    (net (code "149") (name "unconnected-(IC3-XTAL1-Pad1)") (class "Default")
      (node (ref "IC3") (pin "1") (pinfunction "XTAL1_1") (pintype "bidirectional"))
    )
    (net (code "150") (name "unconnected-(IC3-XTAL2{slash}PC0-Pad2)") (class "Default")
      (node (ref "IC3") (pin "2") (pinfunction "XTAL2/PC0_2") (pintype "bidirectional"))
    )
    (net (code "151") (name "unconnected-(IC3-{slash}RESET(PC1)-Pad24)") (class "Default")
      (node (ref "IC3") (pin "24") (pinfunction "/RESET(PC1)_24") (pintype "bidirectional"))
    )
    (net (code "152") (name "unconnected-(REG1.2-VOUT2-Pad2)") (class "Default")
      (node (ref "REG1.2") (pin "2") (pinfunction "VOUT2_2") (pintype "bidirectional"))
    )
    (net (code "153") (name "unconnected-(REG2.5-VOUT2-Pad2)") (class "Default")
      (node (ref "REG2.5") (pin "2") (pinfunction "VOUT2_2") (pintype "bidirectional"))
    )
    (net (code "154") (name "unconnected-(U$2-TRI-PadENA)") (class "Default")
      (node (ref "U$2") (pin "ENA") (pinfunction "TRI_ENA") (pintype "input"))
    )
    (net (code "155") (name "unconnected-(U$4-VOUT2-Pad2)") (class "Default")
      (node (ref "U$4") (pin "2") (pinfunction "VOUT2_2") (pintype "bidirectional"))
    )
    (net (code "156") (name "unconnected-(U$5-GND-Pad1)") (class "Default")
      (node (ref "U$5") (pin "1") (pinfunction "GND_1") (pintype "bidirectional"))
    )
    (net (code "157") (name "unconnected-(U$5-VCC-Pad4)") (class "Default")
      (node (ref "U$5") (pin "4") (pinfunction "VCC_4") (pintype "bidirectional"))
    )
    (net (code "158") (name "unconnected-(U$5-VOUT1-Pad2)") (class "Default")
      (node (ref "U$5") (pin "2") (pinfunction "VOUT1_2") (pintype "output"))
    )
    (net (code "159") (name "unconnected-(U$5-VOUT2-Pad3)") (class "Default")
      (node (ref "U$5") (pin "3") (pinfunction "VOUT2_3") (pintype "output"))
    )
    (net (code "160") (name "unconnected-(U$5-VOUT3-Pad6)") (class "Default")
      (node (ref "U$5") (pin "6") (pinfunction "VOUT3_6") (pintype "output"))
    )
    (net (code "161") (name "unconnected-(U$5-VOUT4-Pad7)") (class "Default")
      (node (ref "U$5") (pin "7") (pinfunction "VOUT4_7") (pintype "output"))
    )
    (net (code "162") (name "unconnected-(U1A-IO_L27P_0-PadP135)") (class "Default")
      (node (ref "U1") (pin "P135") (pinfunction "IO_L27P_0_P135") (pintype "bidirectional"))
    )
    (net (code "163") (name "unconnected-(U1A-IO_L30N_0-PadP132)") (class "Default")
      (node (ref "U1") (pin "P132") (pinfunction "IO_L30N_0_P132") (pintype "bidirectional"))
    )
    (net (code "164") (name "unconnected-(U1A-IO_L30P_0-PadP131)") (class "Default")
      (node (ref "U1") (pin "P131") (pinfunction "IO_L30P_0_P131") (pintype "bidirectional"))
    )
    (net (code "165") (name "unconnected-(U1A-IO_L31N_0-PadP130)") (class "Default")
      (node (ref "U1") (pin "P130") (pinfunction "IO_L31N_0_P130") (pintype "bidirectional"))
    )
    (net (code "166") (name "unconnected-(U1A-IO_L31P_0VREF_0-PadP129)") (class "Default")
      (node (ref "U1") (pin "P129") (pinfunction "IO_L31P_0VREF_0_P129") (pintype "bidirectional"))
    )
    (net (code "167") (name "unconnected-(U1A-IO_L32N_0GCLK7-PadP128)") (class "Default")
      (node (ref "U1") (pin "P128") (pinfunction "IO_L32N_0GCLK7_P128") (pintype "bidirectional"))
    )
    (net (code "168") (name "unconnected-(U1A-IO_L32P_0GCLK6-PadP127)") (class "Default")
      (node (ref "U1") (pin "P127") (pinfunction "IO_L32P_0GCLK6_P127") (pintype "bidirectional"))
    )
    (net (code "169") (name "unconnected-(U1C-IO-PadP116)") (class "Default")
      (node (ref "U1") (pin "P116") (pinfunction "IO_P116") (pintype "bidirectional"))
    )
    (net (code "170") (name "unconnected-(U1C-IO_L01N_1VRP_1-PadP113)") (class "Default")
      (node (ref "U1") (pin "P113") (pinfunction "IO_L01N_1VRP_1_P113") (pintype "bidirectional"))
    )
    (net (code "171") (name "unconnected-(U1C-IO_L01P_1VRN_1-PadP112)") (class "Default")
      (node (ref "U1") (pin "P112") (pinfunction "IO_L01P_1VRN_1_P112") (pintype "bidirectional"))
    )
    (net (code "172") (name "unconnected-(U1C-IO_L28N_1-PadP119)") (class "Default")
      (node (ref "U1") (pin "P119") (pinfunction "IO_L28N_1_P119") (pintype "bidirectional"))
    )
    (net (code "173") (name "unconnected-(U1C-IO_L28P_1-PadP118)") (class "Default")
      (node (ref "U1") (pin "P118") (pinfunction "IO_L28P_1_P118") (pintype "bidirectional"))
    )
    (net (code "174") (name "unconnected-(U1C-IO_L31N_1VREF_1-PadP123)") (class "Default")
      (node (ref "U1") (pin "P123") (pinfunction "IO_L31N_1VREF_1_P123") (pintype "bidirectional"))
    )
    (net (code "175") (name "unconnected-(U1C-IO_L31P_1-PadP122)") (class "Default")
      (node (ref "U1") (pin "P122") (pinfunction "IO_L31P_1_P122") (pintype "bidirectional"))
    )
    (net (code "176") (name "unconnected-(U1C-IO_L32N_1GCLK5-PadP125)") (class "Default")
      (node (ref "U1") (pin "P125") (pinfunction "IO_L32N_1GCLK5_P125") (pintype "bidirectional"))
    )
    (net (code "177") (name "unconnected-(U1C-IO_L32P_1GCLK4-PadP124)") (class "Default")
      (node (ref "U1") (pin "P124") (pinfunction "IO_L32P_1GCLK4_P124") (pintype "bidirectional"))
    )
    (net (code "178") (name "unconnected-(U1J-IO_L01N_6VRP_6-PadP36)") (class "Default")
      (node (ref "U1") (pin "P36") (pinfunction "IO_L01N_6VRP_6_P36") (pintype "bidirectional"))
    )
    (net (code "179") (name "unconnected-(U1J-IO_L01P_6VRN_6-PadP35)") (class "Default")
      (node (ref "U1") (pin "P35") (pinfunction "IO_L01P_6VRN_6_P35") (pintype "bidirectional"))
    )
    (net (code "180") (name "unconnected-(U1J-IO_L20N_6-PadP33)") (class "Default")
      (node (ref "U1") (pin "P33") (pinfunction "IO_L20N_6_P33") (pintype "bidirectional"))
    )
    (net (code "181") (name "unconnected-(U1J-IO_L20P_6-PadP32)") (class "Default")
      (node (ref "U1") (pin "P32") (pinfunction "IO_L20P_6_P32") (pintype "bidirectional"))
    )
    (net (code "182") (name "unconnected-(U1J-IO_L21N_6-PadP31)") (class "Default")
      (node (ref "U1") (pin "P31") (pinfunction "IO_L21N_6_P31") (pintype "bidirectional"))
    )
    (net (code "183") (name "unconnected-(U1J-IO_L21P_6-PadP30)") (class "Default")
      (node (ref "U1") (pin "P30") (pinfunction "IO_L21P_6_P30") (pintype "bidirectional"))
    )
    (net (code "184") (name "unconnected-(U1J-IO_L22N_6-PadP28)") (class "Default")
      (node (ref "U1") (pin "P28") (pinfunction "IO_L22N_6_P28") (pintype "bidirectional"))
    )
    (net (code "185") (name "unconnected-(U1J-IO_L22P_6-PadP27)") (class "Default")
      (node (ref "U1") (pin "P27") (pinfunction "IO_L22P_6_P27") (pintype "bidirectional"))
    )
    (net (code "186") (name "unconnected-(U1J-IO_L23N_6-PadP26)") (class "Default")
      (node (ref "U1") (pin "P26") (pinfunction "IO_L23N_6_P26") (pintype "bidirectional"))
    )
    (net (code "187") (name "unconnected-(U1J-IO_L23P_6-PadP25)") (class "Default")
      (node (ref "U1") (pin "P25") (pinfunction "IO_L23P_6_P25") (pintype "bidirectional"))
    )
    (net (code "188") (name "unconnected-(U1J-IO_L24N_6VREF_6-PadP24)") (class "Default")
      (node (ref "U1") (pin "P24") (pinfunction "IO_L24N_6VREF_6_P24") (pintype "bidirectional"))
    )
    (net (code "189") (name "unconnected-(U1J-IO_L24P_6-PadP23)") (class "Default")
      (node (ref "U1") (pin "P23") (pinfunction "IO_L24P_6_P23") (pintype "bidirectional"))
    )
    (net (code "190") (name "unconnected-(U1J-IO_L40N_6-PadP21)") (class "Default")
      (node (ref "U1") (pin "P21") (pinfunction "IO_L40N_6_P21") (pintype "bidirectional"))
    )
    (net (code "191") (name "unconnected-(U1J-IO_L40P_6VREF_6-PadP20)") (class "Default")
      (node (ref "U1") (pin "P20") (pinfunction "IO_L40P_6VREF_6_P20") (pintype "bidirectional"))
    )
    (net (code "192") (name "unconnected-(U1L-IOVREF_7-PadP4)") (class "Default")
      (node (ref "U1") (pin "P4") (pinfunction "IOVREF_7_P4") (pintype "bidirectional"))
    )
    (net (code "193") (name "unconnected-(U1L-IO_L20N_7-PadP6)") (class "Default")
      (node (ref "U1") (pin "P6") (pinfunction "IO_L20N_7_P6") (pintype "bidirectional"))
    )
    (net (code "194") (name "unconnected-(U1L-IO_L20P_7-PadP5)") (class "Default")
      (node (ref "U1") (pin "P5") (pinfunction "IO_L20P_7_P5") (pintype "bidirectional"))
    )
    (net (code "195") (name "unconnected-(U1L-IO_L21N_7-PadP8)") (class "Default")
      (node (ref "U1") (pin "P8") (pinfunction "IO_L21N_7_P8") (pintype "bidirectional"))
    )
    (net (code "196") (name "unconnected-(U1L-IO_L21P_7-PadP7)") (class "Default")
      (node (ref "U1") (pin "P7") (pinfunction "IO_L21P_7_P7") (pintype "bidirectional"))
    )
    (net (code "197") (name "unconnected-(U1L-IO_L22N_7-PadP11)") (class "Default")
      (node (ref "U1") (pin "P11") (pinfunction "IO_L22N_7_P11") (pintype "bidirectional"))
    )
    (net (code "198") (name "unconnected-(U1L-IO_L22P_7-PadP10)") (class "Default")
      (node (ref "U1") (pin "P10") (pinfunction "IO_L22P_7_P10") (pintype "bidirectional"))
    )
    (net (code "199") (name "unconnected-(U1L-IO_L23N_7-PadP13)") (class "Default")
      (node (ref "U1") (pin "P13") (pinfunction "IO_L23N_7_P13") (pintype "bidirectional"))
    )
    (net (code "200") (name "unconnected-(U1L-IO_L23P_7-PadP12)") (class "Default")
      (node (ref "U1") (pin "P12") (pinfunction "IO_L23P_7_P12") (pintype "bidirectional"))
    )
    (net (code "201") (name "unconnected-(U1L-IO_L24N_7-PadP15)") (class "Default")
      (node (ref "U1") (pin "P15") (pinfunction "IO_L24N_7_P15") (pintype "bidirectional"))
    )
    (net (code "202") (name "unconnected-(U1L-IO_L24P_7-PadP14)") (class "Default")
      (node (ref "U1") (pin "P14") (pinfunction "IO_L24P_7_P14") (pintype "bidirectional"))
    )
    (net (code "203") (name "unconnected-(U1L-IO_L40N_7VREF_7-PadP18)") (class "Default")
      (node (ref "U1") (pin "P18") (pinfunction "IO_L40N_7VREF_7_P18") (pintype "bidirectional"))
    )
    (net (code "204") (name "unconnected-(U1L-IO_L40P_7-PadP17)") (class "Default")
      (node (ref "U1") (pin "P17") (pinfunction "IO_L40P_7_P17") (pintype "bidirectional"))
    )
    (net (code "205") (name "unconnected-(U1N-HSWAP_EN-PadP142)") (class "Default")
      (node (ref "U1") (pin "P142") (pinfunction "HSWAP_EN_P142") (pintype "bidirectional"))
    )
    (net (code "206") (name "unconnected-(X1-3-Pad2)") (class "Default")
      (node (ref "X1") (pin "2") (pinfunction "3_2") (pintype "passive"))
    )
    (net (code "207") (name "unconnected-(X2-Pad10)") (class "Default")
      (node (ref "X2") (pin "10") (pinfunction "10_10") (pintype "passive"))
    )
    (net (code "208") (name "unconnected-(X2-Pad12)") (class "Default")
      (node (ref "X2") (pin "12") (pinfunction "12_12") (pintype "passive"))
    )
    (net (code "209") (name "unconnected-(X3-Pad2)") (class "Default")
      (node (ref "X3") (pin "2") (pinfunction "2_2") (pintype "passive"))
    )
    (net (code "210") (name "unconnected-(X3-Pad8)") (class "Default")
      (node (ref "X3") (pin "8") (pinfunction "8_8") (pintype "passive"))
    )
    (net (code "211") (name "unconnected-(X4-PadG2)") (class "Default")
      (node (ref "X4") (pin "G2") (pinfunction "G2_G2") (pintype "passive"))
    )
    (net (code "212") (name "unconnected-(X5-PadG2)") (class "Default")
      (node (ref "X5") (pin "G2") (pinfunction "G2_G2") (pintype "passive"))
    )
    (net (code "213") (name "unconnected-(X6-Pad1)") (class "Default")
      (node (ref "X6") (pin "1") (pinfunction "1_1") (pintype "passive"))
    )
  )
)
